# PT_2016_PB_4lyr_Rev2.net
KiCad netlist of a schematic drawn in EAGLE
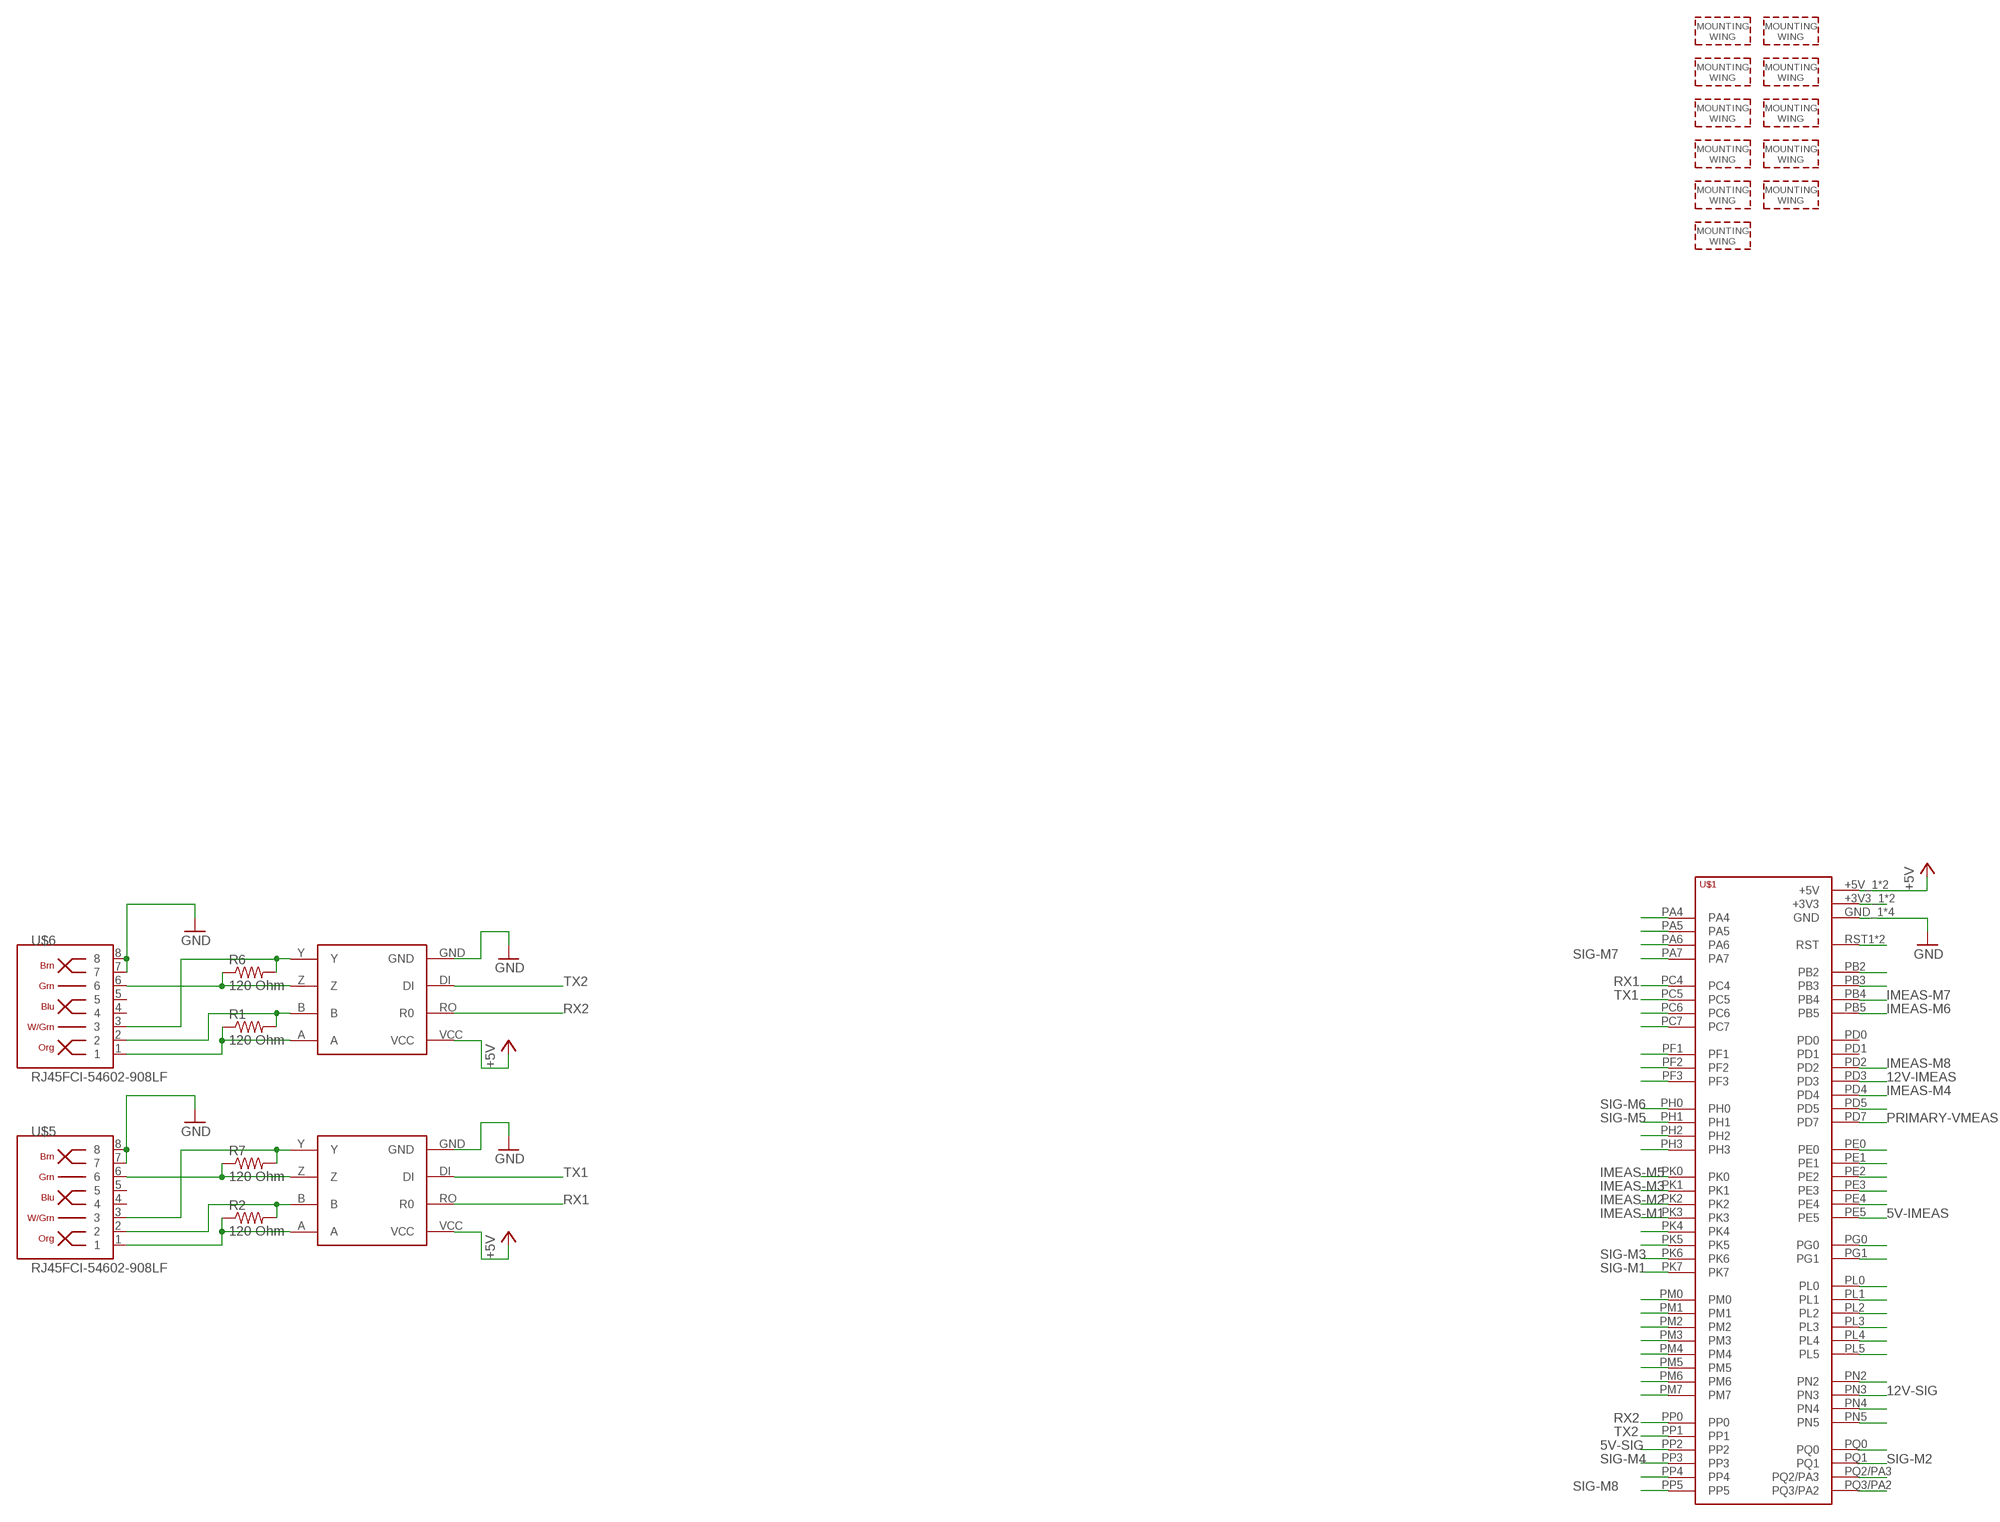
[diagram p0: schematic, sheet 1, part 1 of 3]
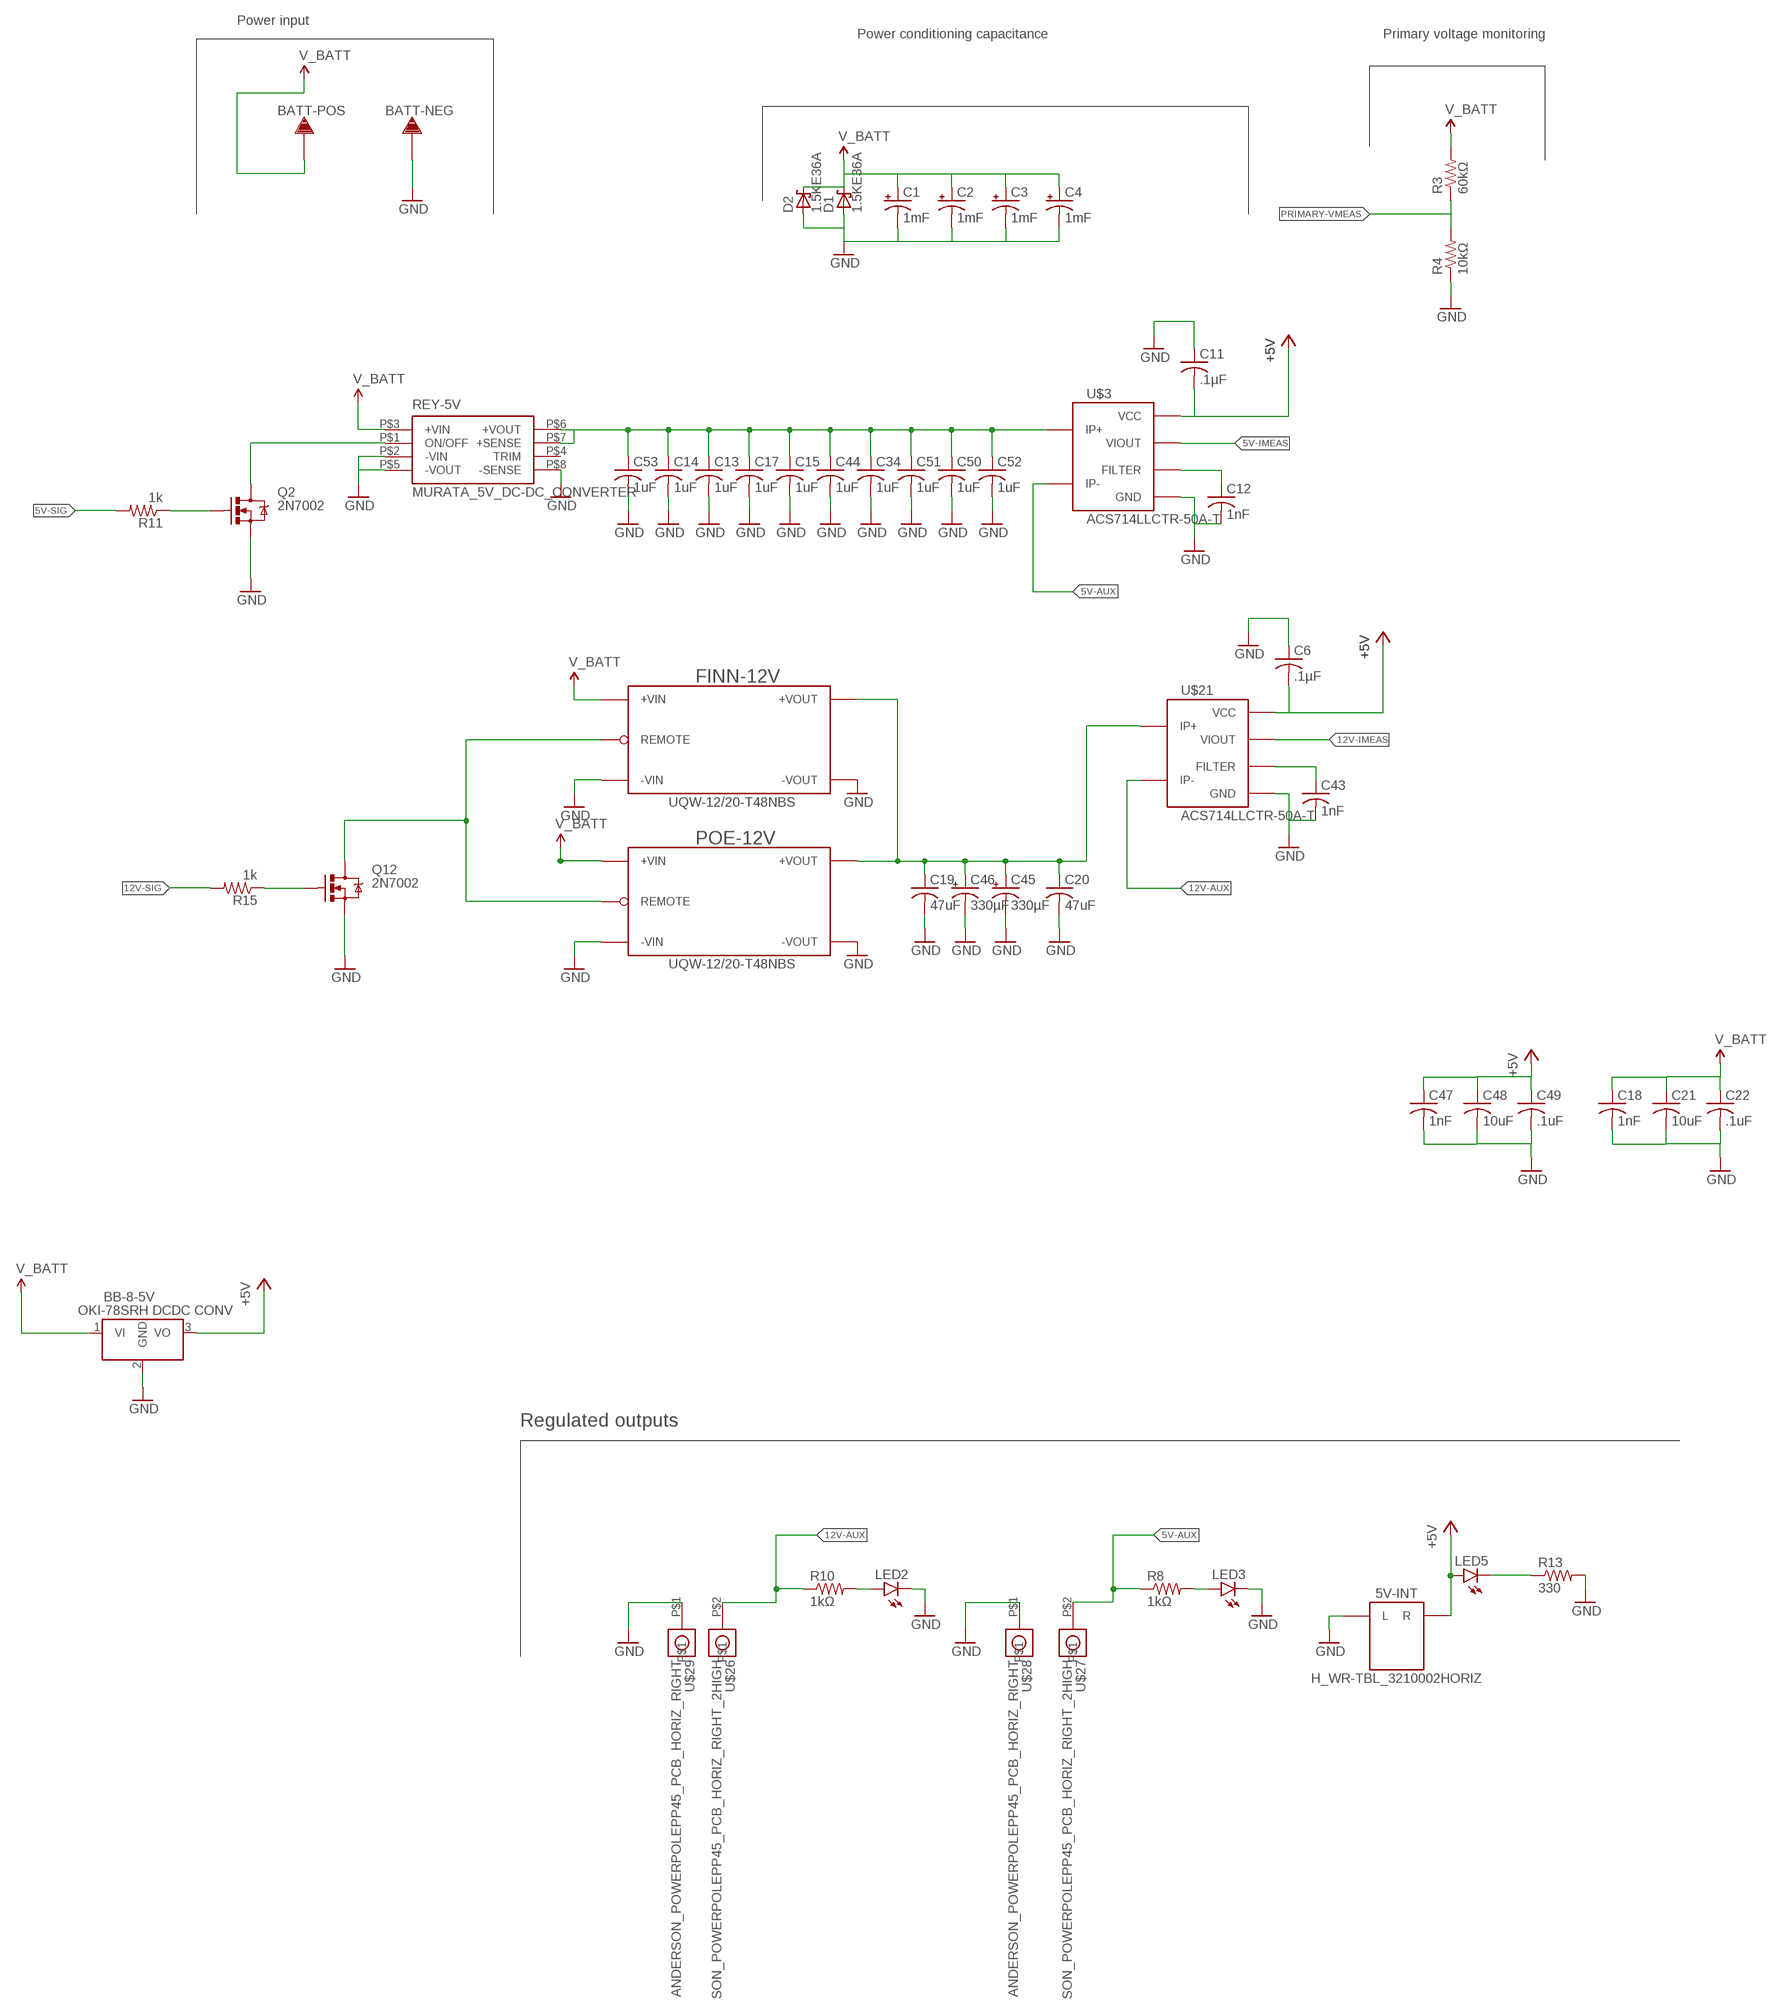
[diagram p1: schematic, sheet 1, part 2 of 3]
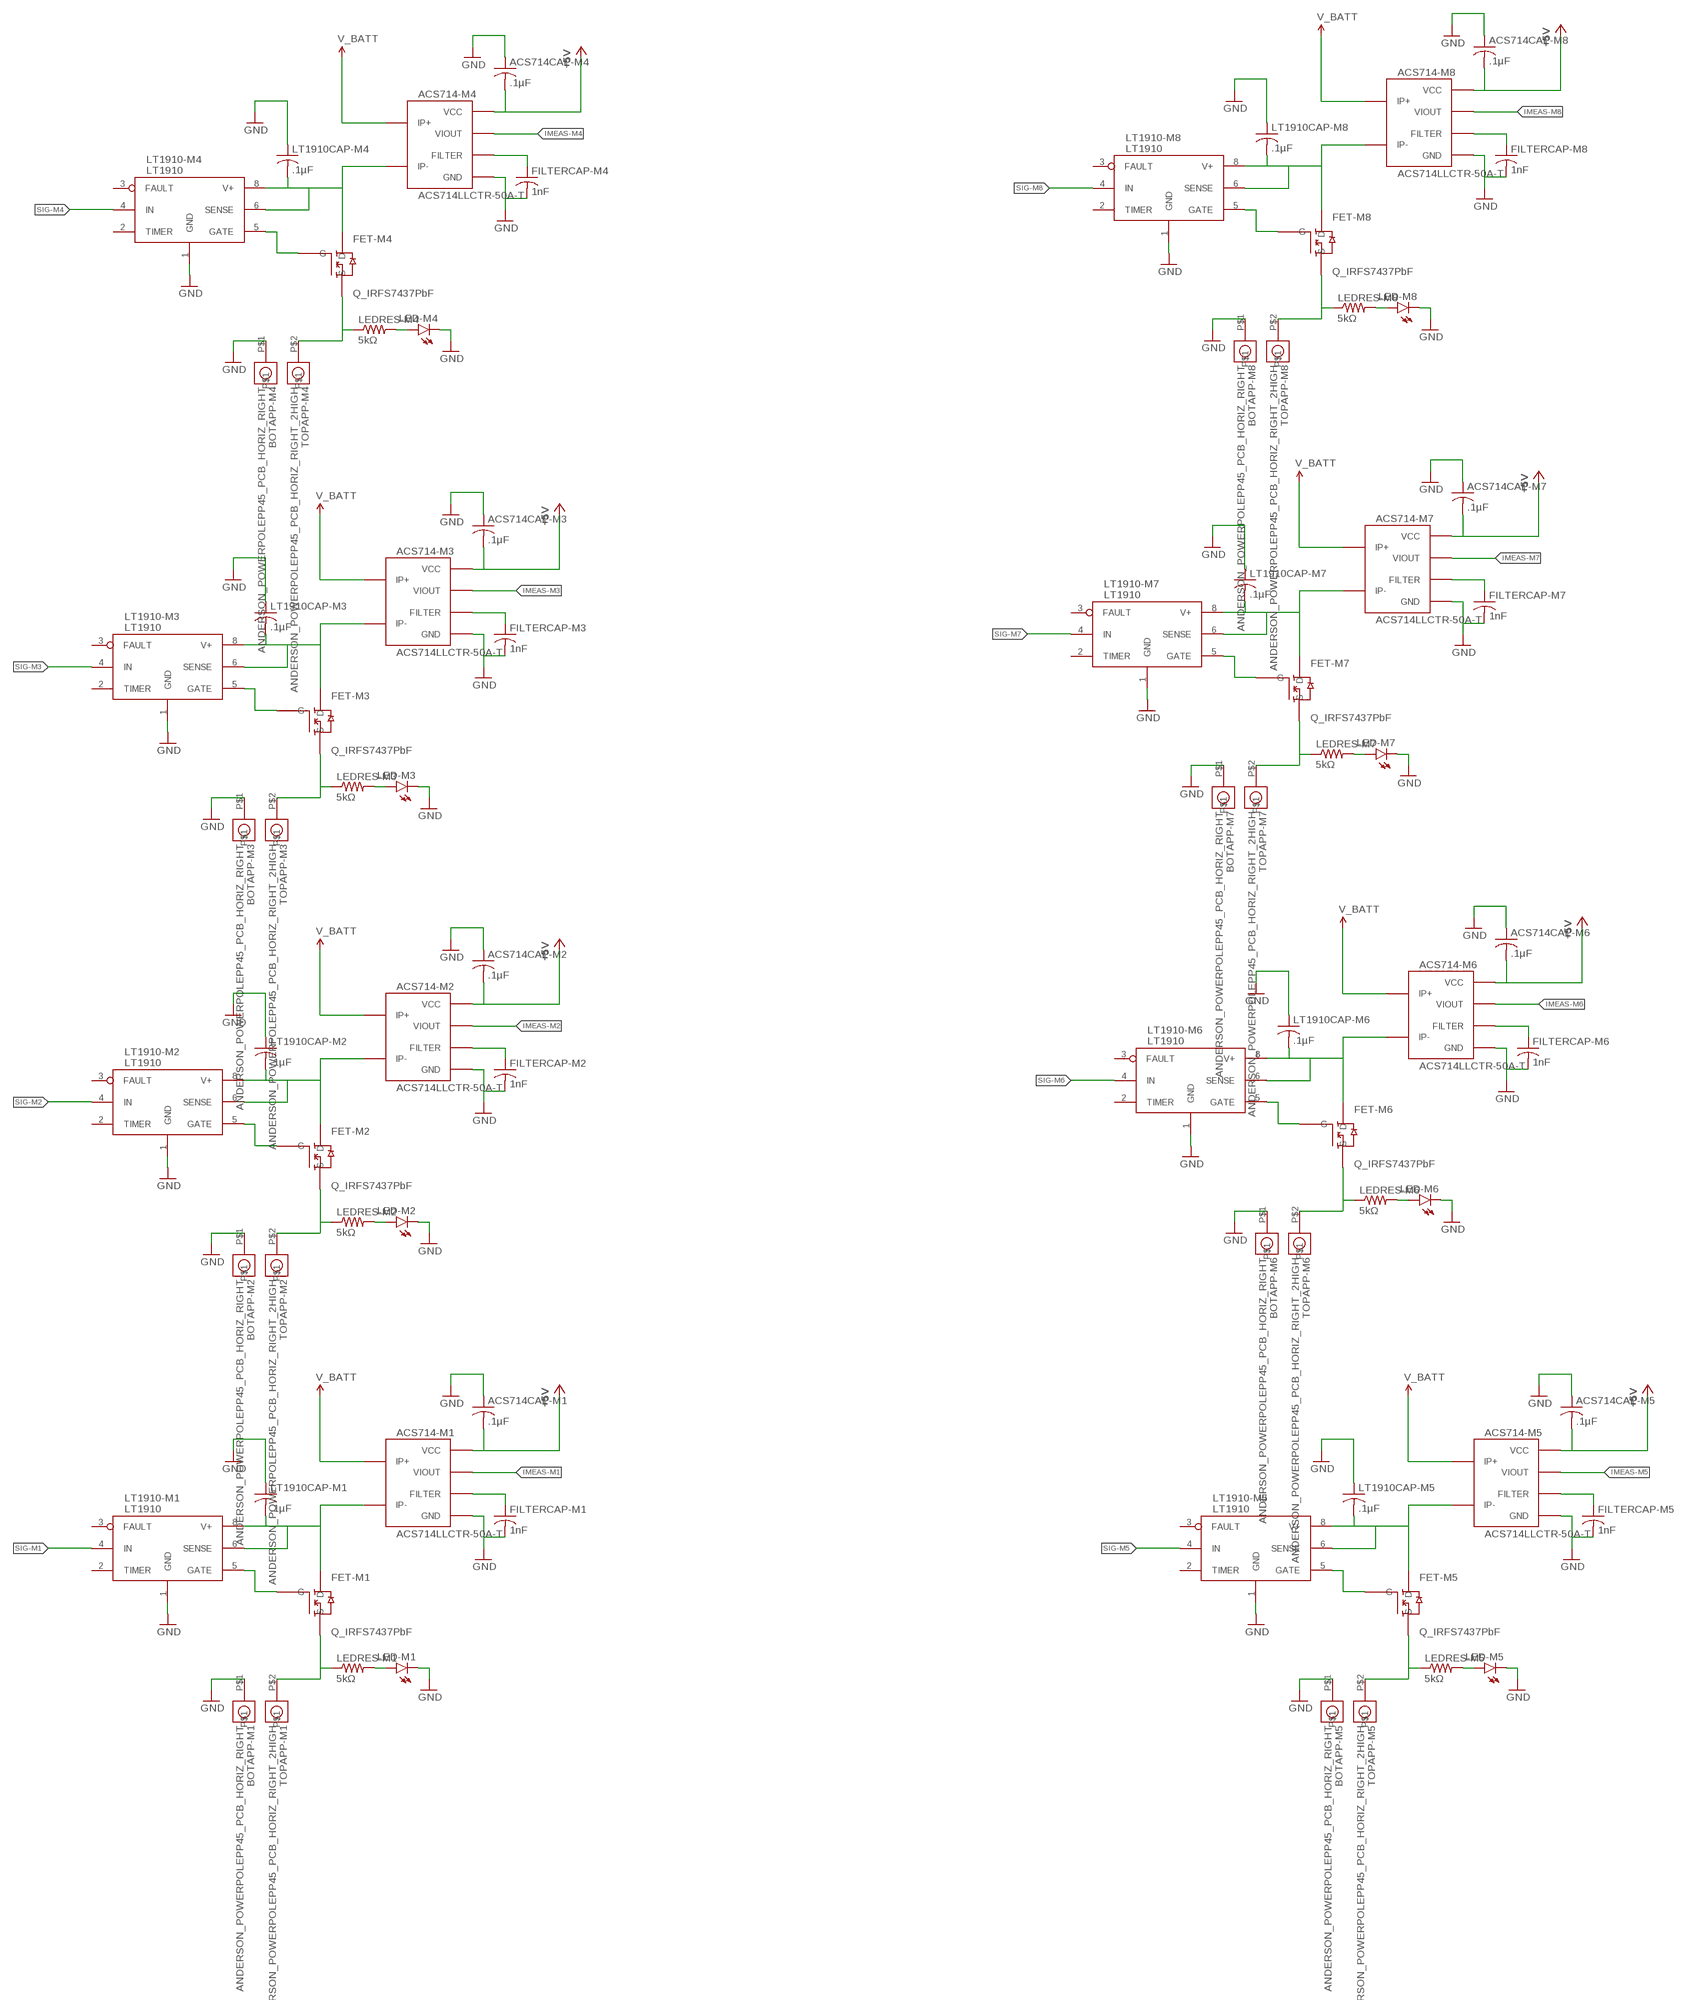
[diagram p2: schematic, sheet 1, part 3 of 3]

(export (version "E")
  (design (tool "Eeschema 10.0.6"))
  (components
    (comp (ref "5V-INT")
      (value "H_WR-TBL_3210002HORIZ")
      (footprint "eagle-import:691322110002")
      (libsource (lib "eagle-import") (part "H_WR-TBL_3210002HORIZ"))
    )
    (comp (ref "ACS714-M1")
      (value "ACS714LLCTR-50A-T")
      (footprint "eagle-import:SOIC8_ACS711")
      (libsource (lib "eagle-import") (part "Q_ACS714"))
    )
    (comp (ref "ACS714-M2")
      (value "ACS714LLCTR-50A-T")
      (footprint "eagle-import:SOIC8_ACS711")
      (libsource (lib "eagle-import") (part "Q_ACS714"))
    )
    (comp (ref "ACS714-M3")
      (value "ACS714LLCTR-50A-T")
      (footprint "eagle-import:SOIC8_ACS711")
      (libsource (lib "eagle-import") (part "Q_ACS714"))
    )
    (comp (ref "ACS714-M4")
      (value "ACS714LLCTR-50A-T")
      (footprint "eagle-import:SOIC8_ACS711")
      (libsource (lib "eagle-import") (part "Q_ACS714"))
    )
    (comp (ref "ACS714-M5")
      (value "ACS714LLCTR-50A-T")
      (footprint "eagle-import:SOIC8_ACS711")
      (libsource (lib "eagle-import") (part "Q_ACS714"))
    )
    (comp (ref "ACS714-M6")
      (value "ACS714LLCTR-50A-T")
      (footprint "eagle-import:SOIC8_ACS711")
      (libsource (lib "eagle-import") (part "Q_ACS714"))
    )
    (comp (ref "ACS714-M7")
      (value "ACS714LLCTR-50A-T")
      (footprint "eagle-import:SOIC8_ACS711")
      (libsource (lib "eagle-import") (part "Q_ACS714"))
    )
    (comp (ref "ACS714-M8")
      (value "ACS714LLCTR-50A-T")
      (footprint "eagle-import:SOIC8_ACS711")
      (libsource (lib "eagle-import") (part "Q_ACS714"))
    )
    (comp (ref "ACS714CAP-M1")
      (value ".1µF")
      (footprint "eagle-import:C1206")
      (libsource (lib "eagle-import") (part "C-USC1206"))
    )
    (comp (ref "ACS714CAP-M2")
      (value ".1µF")
      (footprint "eagle-import:C1206")
      (libsource (lib "eagle-import") (part "C-USC1206"))
    )
    (comp (ref "ACS714CAP-M3")
      (value ".1µF")
      (footprint "eagle-import:C1206")
      (libsource (lib "eagle-import") (part "C-USC1206"))
    )
    (comp (ref "ACS714CAP-M4")
      (value ".1µF")
      (footprint "eagle-import:C1206")
      (libsource (lib "eagle-import") (part "C-USC1206"))
    )
    (comp (ref "ACS714CAP-M5")
      (value ".1µF")
      (footprint "eagle-import:C1206")
      (libsource (lib "eagle-import") (part "C-USC1206"))
    )
    (comp (ref "ACS714CAP-M6")
      (value ".1µF")
      (footprint "eagle-import:C1206")
      (libsource (lib "eagle-import") (part "C-USC1206"))
    )
    (comp (ref "ACS714CAP-M7")
      (value ".1µF")
      (footprint "eagle-import:C1206")
      (libsource (lib "eagle-import") (part "C-USC1206"))
    )
    (comp (ref "ACS714CAP-M8")
      (value ".1µF")
      (footprint "eagle-import:C1206")
      (libsource (lib "eagle-import") (part "C-USC1206"))
    )
    (comp (ref "BATT-NEG")
      (value "TERMINAL_HOLE")
      (footprint "eagle-import:LARGE_TERMINAL_HOLE")
      (libsource (lib "eagle-import") (part "TERMINAL_HOLE"))
    )
    (comp (ref "BATT-POS")
      (value "TERMINAL_HOLE")
      (footprint "eagle-import:LARGE_TERMINAL_HOLE")
      (libsource (lib "eagle-import") (part "TERMINAL_HOLE"))
    )
    (comp (ref "BB-8-5V")
      (value "Q_OKI-78SR")
      (footprint "eagle-import:OKI-78SRH")
      (libsource (lib "eagle-import") (part "Q_OKI-78SR"))
    )
    (comp (ref "BOTAPP-M1")
      (value "ANDERSON_POWERPOLEPP45_PCB_HORIZ_RIGHT")
      (footprint "eagle-import:APP45_PCB_HORIZ_RIGHT")
      (libsource (lib "eagle-import") (part "ANDERSON_POWERPOLEPP45_PCB_HORIZ_RIGHT"))
    )
    (comp (ref "BOTAPP-M2")
      (value "ANDERSON_POWERPOLEPP45_PCB_HORIZ_RIGHT")
      (footprint "eagle-import:APP45_PCB_HORIZ_RIGHT")
      (libsource (lib "eagle-import") (part "ANDERSON_POWERPOLEPP45_PCB_HORIZ_RIGHT"))
    )
    (comp (ref "BOTAPP-M3")
      (value "ANDERSON_POWERPOLEPP45_PCB_HORIZ_RIGHT")
      (footprint "eagle-import:APP45_PCB_HORIZ_RIGHT")
      (libsource (lib "eagle-import") (part "ANDERSON_POWERPOLEPP45_PCB_HORIZ_RIGHT"))
    )
    (comp (ref "BOTAPP-M4")
      (value "ANDERSON_POWERPOLEPP45_PCB_HORIZ_RIGHT")
      (footprint "eagle-import:APP45_PCB_HORIZ_RIGHT")
      (libsource (lib "eagle-import") (part "ANDERSON_POWERPOLEPP45_PCB_HORIZ_RIGHT"))
    )
    (comp (ref "BOTAPP-M5")
      (value "ANDERSON_POWERPOLEPP45_PCB_HORIZ_RIGHT")
      (footprint "eagle-import:APP45_PCB_HORIZ_RIGHT")
      (libsource (lib "eagle-import") (part "ANDERSON_POWERPOLEPP45_PCB_HORIZ_RIGHT"))
    )
    (comp (ref "BOTAPP-M6")
      (value "ANDERSON_POWERPOLEPP45_PCB_HORIZ_RIGHT")
      (footprint "eagle-import:APP45_PCB_HORIZ_RIGHT")
      (libsource (lib "eagle-import") (part "ANDERSON_POWERPOLEPP45_PCB_HORIZ_RIGHT"))
    )
    (comp (ref "BOTAPP-M7")
      (value "ANDERSON_POWERPOLEPP45_PCB_HORIZ_RIGHT")
      (footprint "eagle-import:APP45_PCB_HORIZ_RIGHT")
      (libsource (lib "eagle-import") (part "ANDERSON_POWERPOLEPP45_PCB_HORIZ_RIGHT"))
    )
    (comp (ref "BOTAPP-M8")
      (value "ANDERSON_POWERPOLEPP45_PCB_HORIZ_RIGHT")
      (footprint "eagle-import:APP45_PCB_HORIZ_RIGHT")
      (libsource (lib "eagle-import") (part "ANDERSON_POWERPOLEPP45_PCB_HORIZ_RIGHT"))
    )
    (comp (ref "C1")
      (value "1mF")
      (footprint "eagle-import:C_12.5MM")
      (libsource (lib "eagle-import") (part "C_POL12.5MM_NORMAL"))
    )
    (comp (ref "C2")
      (value "1mF")
      (footprint "eagle-import:C_12.5MM")
      (libsource (lib "eagle-import") (part "C_POL12.5MM_NORMAL"))
    )
    (comp (ref "C3")
      (value "1mF")
      (footprint "eagle-import:C_12.5MM")
      (libsource (lib "eagle-import") (part "C_POL12.5MM_NORMAL"))
    )
    (comp (ref "C4")
      (value "1mF")
      (footprint "eagle-import:C_12.5MM")
      (libsource (lib "eagle-import") (part "C_POL12.5MM_NORMAL"))
    )
    (comp (ref "C6")
      (value ".1µF")
      (footprint "eagle-import:C1206")
      (libsource (lib "eagle-import") (part "C-USC1206"))
    )
    (comp (ref "C11")
      (value ".1µF")
      (footprint "eagle-import:C1206")
      (libsource (lib "eagle-import") (part "C-USC1206"))
    )
    (comp (ref "C12")
      (value "1nF")
      (footprint "eagle-import:C1206")
      (libsource (lib "eagle-import") (part "C-USC1206"))
    )
    (comp (ref "C13")
      (value "1uF")
      (footprint "eagle-import:C1206")
      (libsource (lib "eagle-import") (part "C-USC1206"))
    )
    (comp (ref "C14")
      (value "1uF")
      (footprint "eagle-import:C1206")
      (libsource (lib "eagle-import") (part "C-USC1206"))
    )
    (comp (ref "C15")
      (value "1uF")
      (footprint "eagle-import:C1206")
      (libsource (lib "eagle-import") (part "C-USC1206"))
    )
    (comp (ref "C17")
      (value "1uF")
      (footprint "eagle-import:C1206")
      (libsource (lib "eagle-import") (part "C-USC1206"))
    )
    (comp (ref "C18")
      (value "1nF")
      (footprint "eagle-import:C1206")
      (libsource (lib "eagle-import") (part "C-USC1206"))
    )
    (comp (ref "C19")
      (value "47uF")
      (footprint "eagle-import:C1206")
      (libsource (lib "eagle-import") (part "C-USC1206"))
    )
    (comp (ref "C20")
      (value "47uF")
      (footprint "eagle-import:C1206")
      (libsource (lib "eagle-import") (part "C-USC1206"))
    )
    (comp (ref "C21")
      (value "10uF")
      (footprint "eagle-import:C1206")
      (libsource (lib "eagle-import") (part "C-USC1206"))
    )
    (comp (ref "C22")
      (value ".1uF")
      (footprint "eagle-import:C1206")
      (libsource (lib "eagle-import") (part "C-USC1206"))
    )
    (comp (ref "C34")
      (value "1uF")
      (footprint "eagle-import:C1206")
      (libsource (lib "eagle-import") (part "C-USC1206"))
    )
    (comp (ref "C43")
      (value "1nF")
      (footprint "eagle-import:C1206")
      (libsource (lib "eagle-import") (part "C-USC1206"))
    )
    (comp (ref "C44")
      (value "1uF")
      (footprint "eagle-import:C1206")
      (libsource (lib "eagle-import") (part "C-USC1206"))
    )
    (comp (ref "C45")
      (value "330µF")
      (footprint "eagle-import:E5-8,5")
      (libsource (lib "eagle-import") (part "CPOL-USE5-8.5"))
    )
    (comp (ref "C46")
      (value "330µF")
      (footprint "eagle-import:E5-8,5")
      (libsource (lib "eagle-import") (part "CPOL-USE5-8.5"))
    )
    (comp (ref "C47")
      (value "1nF")
      (footprint "eagle-import:C1206")
      (libsource (lib "eagle-import") (part "C-USC1206"))
    )
    (comp (ref "C48")
      (value "10uF")
      (footprint "eagle-import:C1206")
      (libsource (lib "eagle-import") (part "C-USC1206"))
    )
    (comp (ref "C49")
      (value ".1uF")
      (footprint "eagle-import:C1206")
      (libsource (lib "eagle-import") (part "C-USC1206"))
    )
    (comp (ref "C50")
      (value "1uF")
      (footprint "eagle-import:C1206")
      (libsource (lib "eagle-import") (part "C-USC1206"))
    )
    (comp (ref "C51")
      (value "1uF")
      (footprint "eagle-import:C1206")
      (libsource (lib "eagle-import") (part "C-USC1206"))
    )
    (comp (ref "C52")
      (value "1uF")
      (footprint "eagle-import:C1206")
      (libsource (lib "eagle-import") (part "C-USC1206"))
    )
    (comp (ref "C53")
      (value "1uF")
      (footprint "eagle-import:C1206")
      (libsource (lib "eagle-import") (part "C-USC1206"))
    )
    (comp (ref "D1")
      (value "1.5KE36A")
      (footprint "eagle-import:CB429-17")
      (libsource (lib "eagle-import") (part "15KEXX"))
    )
    (comp (ref "D2")
      (value "1.5KE36A")
      (footprint "eagle-import:CB429-17")
      (libsource (lib "eagle-import") (part "15KEXX"))
    )
    (comp (ref "FET-M1")
      (value "Q_IRFS7437PbF")
      (footprint "eagle-import:D2PACK")
      (libsource (lib "eagle-import") (part "Q_IRF7437SMD"))
    )
    (comp (ref "FET-M2")
      (value "Q_IRFS7437PbF")
      (footprint "eagle-import:D2PACK")
      (libsource (lib "eagle-import") (part "Q_IRF7437SMD"))
    )
    (comp (ref "FET-M3")
      (value "Q_IRFS7437PbF")
      (footprint "eagle-import:D2PACK")
      (libsource (lib "eagle-import") (part "Q_IRF7437SMD"))
    )
    (comp (ref "FET-M4")
      (value "Q_IRFS7437PbF")
      (footprint "eagle-import:D2PACK")
      (libsource (lib "eagle-import") (part "Q_IRF7437SMD"))
    )
    (comp (ref "FET-M5")
      (value "Q_IRFS7437PbF")
      (footprint "eagle-import:D2PACK")
      (libsource (lib "eagle-import") (part "Q_IRF7437SMD"))
    )
    (comp (ref "FET-M6")
      (value "Q_IRFS7437PbF")
      (footprint "eagle-import:D2PACK")
      (libsource (lib "eagle-import") (part "Q_IRF7437SMD"))
    )
    (comp (ref "FET-M7")
      (value "Q_IRFS7437PbF")
      (footprint "eagle-import:D2PACK")
      (libsource (lib "eagle-import") (part "Q_IRF7437SMD"))
    )
    (comp (ref "FET-M8")
      (value "Q_IRFS7437PbF")
      (footprint "eagle-import:D2PACK")
      (libsource (lib "eagle-import") (part "Q_IRF7437SMD"))
    )
    (comp (ref "FILTERCAP-M1")
      (value "1nF")
      (footprint "eagle-import:C1206")
      (libsource (lib "eagle-import") (part "C-USC1206"))
    )
    (comp (ref "FILTERCAP-M2")
      (value "1nF")
      (footprint "eagle-import:C1206")
      (libsource (lib "eagle-import") (part "C-USC1206"))
    )
    (comp (ref "FILTERCAP-M3")
      (value "1nF")
      (footprint "eagle-import:C1206")
      (libsource (lib "eagle-import") (part "C-USC1206"))
    )
    (comp (ref "FILTERCAP-M4")
      (value "1nF")
      (footprint "eagle-import:C1206")
      (libsource (lib "eagle-import") (part "C-USC1206"))
    )
    (comp (ref "FILTERCAP-M5")
      (value "1nF")
      (footprint "eagle-import:C1206")
      (libsource (lib "eagle-import") (part "C-USC1206"))
    )
    (comp (ref "FILTERCAP-M6")
      (value "1nF")
      (footprint "eagle-import:C1206")
      (libsource (lib "eagle-import") (part "C-USC1206"))
    )
    (comp (ref "FILTERCAP-M7")
      (value "1nF")
      (footprint "eagle-import:C1206")
      (libsource (lib "eagle-import") (part "C-USC1206"))
    )
    (comp (ref "FILTERCAP-M8")
      (value "1nF")
      (footprint "eagle-import:C1206")
      (libsource (lib "eagle-import") (part "C-USC1206"))
    )
    (comp (ref "FINN-12V")
      (value "UQW-12/20-T48NBS")
      (footprint "eagle-import:U-T48-QB-NO_TRIM")
      (libsource (lib "eagle-import") (part "UQW-12/20-T48NBS"))
    )
    (comp (ref "LED-M1")
      (value "LED1206")
      (footprint "eagle-import:LED-1206")
      (libsource (lib "eagle-import") (part "LED1206"))
    )
    (comp (ref "LED-M2")
      (value "LED1206")
      (footprint "eagle-import:LED-1206")
      (libsource (lib "eagle-import") (part "LED1206"))
    )
    (comp (ref "LED-M3")
      (value "LED1206")
      (footprint "eagle-import:LED-1206")
      (libsource (lib "eagle-import") (part "LED1206"))
    )
    (comp (ref "LED-M4")
      (value "LED1206")
      (footprint "eagle-import:LED-1206")
      (libsource (lib "eagle-import") (part "LED1206"))
    )
    (comp (ref "LED-M5")
      (value "LED1206")
      (footprint "eagle-import:LED-1206")
      (libsource (lib "eagle-import") (part "LED1206"))
    )
    (comp (ref "LED-M6")
      (value "LED1206")
      (footprint "eagle-import:LED-1206")
      (libsource (lib "eagle-import") (part "LED1206"))
    )
    (comp (ref "LED-M7")
      (value "LED1206")
      (footprint "eagle-import:LED-1206")
      (libsource (lib "eagle-import") (part "LED1206"))
    )
    (comp (ref "LED-M8")
      (value "LED1206")
      (footprint "eagle-import:LED-1206")
      (libsource (lib "eagle-import") (part "LED1206"))
    )
    (comp (ref "LED2")
      (value "LED1206")
      (footprint "eagle-import:LED-1206")
      (libsource (lib "eagle-import") (part "LED1206"))
    )
    (comp (ref "LED3")
      (value "LED1206")
      (footprint "eagle-import:LED-1206")
      (libsource (lib "eagle-import") (part "LED1206"))
    )
    (comp (ref "LED5")
      (value "LED1206")
      (footprint "eagle-import:LED-1206")
      (libsource (lib "eagle-import") (part "LED1206"))
    )
    (comp (ref "LEDRES-M1")
      (value "5kΩ")
      (footprint "eagle-import:1206")
      (libsource (lib "eagle-import") (part "RESISTOR1206"))
    )
    (comp (ref "LEDRES-M2")
      (value "5kΩ")
      (footprint "eagle-import:1206")
      (libsource (lib "eagle-import") (part "RESISTOR1206"))
    )
    (comp (ref "LEDRES-M3")
      (value "5kΩ")
      (footprint "eagle-import:1206")
      (libsource (lib "eagle-import") (part "RESISTOR1206"))
    )
    (comp (ref "LEDRES-M4")
      (value "5kΩ")
      (footprint "eagle-import:1206")
      (libsource (lib "eagle-import") (part "RESISTOR1206"))
    )
    (comp (ref "LEDRES-M5")
      (value "5kΩ")
      (footprint "eagle-import:1206")
      (libsource (lib "eagle-import") (part "RESISTOR1206"))
    )
    (comp (ref "LEDRES-M6")
      (value "5kΩ")
      (footprint "eagle-import:1206")
      (libsource (lib "eagle-import") (part "RESISTOR1206"))
    )
    (comp (ref "LEDRES-M7")
      (value "5kΩ")
      (footprint "eagle-import:1206")
      (libsource (lib "eagle-import") (part "RESISTOR1206"))
    )
    (comp (ref "LEDRES-M8")
      (value "5kΩ")
      (footprint "eagle-import:1206")
      (libsource (lib "eagle-import") (part "RESISTOR1206"))
    )
    (comp (ref "LT1910-M1")
      (value "LT1910")
      (footprint "eagle-import:SO8")
      (libsource (lib "eagle-import") (part "LT1910"))
    )
    (comp (ref "LT1910-M2")
      (value "LT1910")
      (footprint "eagle-import:SO8")
      (libsource (lib "eagle-import") (part "LT1910"))
    )
    (comp (ref "LT1910-M3")
      (value "LT1910")
      (footprint "eagle-import:SO8")
      (libsource (lib "eagle-import") (part "LT1910"))
    )
    (comp (ref "LT1910-M4")
      (value "LT1910")
      (footprint "eagle-import:SO8")
      (libsource (lib "eagle-import") (part "LT1910"))
    )
    (comp (ref "LT1910-M5")
      (value "LT1910")
      (footprint "eagle-import:SO8")
      (libsource (lib "eagle-import") (part "LT1910"))
    )
    (comp (ref "LT1910-M6")
      (value "LT1910")
      (footprint "eagle-import:SO8")
      (libsource (lib "eagle-import") (part "LT1910"))
    )
    (comp (ref "LT1910-M7")
      (value "LT1910")
      (footprint "eagle-import:SO8")
      (libsource (lib "eagle-import") (part "LT1910"))
    )
    (comp (ref "LT1910-M8")
      (value "LT1910")
      (footprint "eagle-import:SO8")
      (libsource (lib "eagle-import") (part "LT1910"))
    )
    (comp (ref "LT1910CAP-M1")
      (value ".1µF")
      (footprint "eagle-import:C1206")
      (libsource (lib "eagle-import") (part "C-USC1206"))
    )
    (comp (ref "LT1910CAP-M2")
      (value ".1µF")
      (footprint "eagle-import:C1206")
      (libsource (lib "eagle-import") (part "C-USC1206"))
    )
    (comp (ref "LT1910CAP-M3")
      (value ".1µF")
      (footprint "eagle-import:C1206")
      (libsource (lib "eagle-import") (part "C-USC1206"))
    )
    (comp (ref "LT1910CAP-M4")
      (value ".1µF")
      (footprint "eagle-import:C1206")
      (libsource (lib "eagle-import") (part "C-USC1206"))
    )
    (comp (ref "LT1910CAP-M5")
      (value ".1µF")
      (footprint "eagle-import:C1206")
      (libsource (lib "eagle-import") (part "C-USC1206"))
    )
    (comp (ref "LT1910CAP-M6")
      (value ".1µF")
      (footprint "eagle-import:C1206")
      (libsource (lib "eagle-import") (part "C-USC1206"))
    )
    (comp (ref "LT1910CAP-M7")
      (value ".1µF")
      (footprint "eagle-import:C1206")
      (libsource (lib "eagle-import") (part "C-USC1206"))
    )
    (comp (ref "LT1910CAP-M8")
      (value ".1µF")
      (footprint "eagle-import:C1206")
      (libsource (lib "eagle-import") (part "C-USC1206"))
    )
    (comp (ref "POE-12V")
      (value "UQW-12/20-T48NBS")
      (footprint "eagle-import:U-T48-QB-NO_TRIM")
      (libsource (lib "eagle-import") (part "UQW-12/20-T48NBS"))
    )
    (comp (ref "Q2")
      (value "2N7002")
      (footprint "eagle-import:SOT323")
      (libsource (lib "eagle-import") (part "MOSFET-NCHANNEL2N7002PW"))
    )
    (comp (ref "Q12")
      (value "2N7002")
      (footprint "eagle-import:SOT323")
      (libsource (lib "eagle-import") (part "MOSFET-NCHANNEL2N7002PW"))
    )
    (comp (ref "R1")
      (value "120 Ohm")
      (footprint "eagle-import:1206")
      (libsource (lib "eagle-import") (part "RESISTOR1206"))
    )
    (comp (ref "R2")
      (value "120 Ohm")
      (footprint "eagle-import:1206")
      (libsource (lib "eagle-import") (part "RESISTOR1206"))
    )
    (comp (ref "R3")
      (value "60kΩ")
      (footprint "eagle-import:R1206")
      (libsource (lib "eagle-import") (part "R-US_R1206"))
    )
    (comp (ref "R4")
      (value "10kΩ")
      (footprint "eagle-import:R1206")
      (libsource (lib "eagle-import") (part "R-US_R1206"))
    )
    (comp (ref "R6")
      (value "120 Ohm")
      (footprint "eagle-import:1206")
      (libsource (lib "eagle-import") (part "RESISTOR1206"))
    )
    (comp (ref "R7")
      (value "120 Ohm")
      (footprint "eagle-import:1206")
      (libsource (lib "eagle-import") (part "RESISTOR1206"))
    )
    (comp (ref "R8")
      (value "1kΩ")
      (footprint "eagle-import:1206")
      (libsource (lib "eagle-import") (part "RESISTOR1206"))
    )
    (comp (ref "R10")
      (value "1kΩ")
      (footprint "eagle-import:1206")
      (libsource (lib "eagle-import") (part "RESISTOR1206"))
    )
    (comp (ref "R11")
      (value "1k")
      (footprint "eagle-import:R1206")
      (libsource (lib "eagle-import") (part "R-US_R1206"))
    )
    (comp (ref "R13")
      (value "330")
      (footprint "eagle-import:1206")
      (libsource (lib "eagle-import") (part "RESISTOR1206"))
    )
    (comp (ref "R15")
      (value "1k")
      (footprint "eagle-import:R1206")
      (libsource (lib "eagle-import") (part "R-US_R1206"))
    )
    (comp (ref "REY-5V")
      (value "MURATA_5V_DC-DC_CONVERTER")
      (footprint "eagle-import:MURATA_5V_DC-DC_CONVERTER")
      (libsource (lib "eagle-import") (part "MURATA_5V_DC-DC_CONVERTER"))
    )
    (comp (ref "TOPAPP-M1")
      (value "ANDERSON_POWERPOLEPP45_PCB_HORIZ_RIGHT_2HIGH")
      (footprint "eagle-import:APP45_PCB_HORIZ_RIGHT_2HIGH")
      (libsource (lib "eagle-import") (part "ANDERSON_POWERPOLEPP45_PCB_HORIZ_RIGHT_2HIGH"))
    )
    (comp (ref "TOPAPP-M2")
      (value "ANDERSON_POWERPOLEPP45_PCB_HORIZ_RIGHT_2HIGH")
      (footprint "eagle-import:APP45_PCB_HORIZ_RIGHT_2HIGH")
      (libsource (lib "eagle-import") (part "ANDERSON_POWERPOLEPP45_PCB_HORIZ_RIGHT_2HIGH"))
    )
    (comp (ref "TOPAPP-M3")
      (value "ANDERSON_POWERPOLEPP45_PCB_HORIZ_RIGHT_2HIGH")
      (footprint "eagle-import:APP45_PCB_HORIZ_RIGHT_2HIGH")
      (libsource (lib "eagle-import") (part "ANDERSON_POWERPOLEPP45_PCB_HORIZ_RIGHT_2HIGH"))
    )
    (comp (ref "TOPAPP-M4")
      (value "ANDERSON_POWERPOLEPP45_PCB_HORIZ_RIGHT_2HIGH")
      (footprint "eagle-import:APP45_PCB_HORIZ_RIGHT_2HIGH")
      (libsource (lib "eagle-import") (part "ANDERSON_POWERPOLEPP45_PCB_HORIZ_RIGHT_2HIGH"))
    )
    (comp (ref "TOPAPP-M5")
      (value "ANDERSON_POWERPOLEPP45_PCB_HORIZ_RIGHT_2HIGH")
      (footprint "eagle-import:APP45_PCB_HORIZ_RIGHT_2HIGH")
      (libsource (lib "eagle-import") (part "ANDERSON_POWERPOLEPP45_PCB_HORIZ_RIGHT_2HIGH"))
    )
    (comp (ref "TOPAPP-M6")
      (value "ANDERSON_POWERPOLEPP45_PCB_HORIZ_RIGHT_2HIGH")
      (footprint "eagle-import:APP45_PCB_HORIZ_RIGHT_2HIGH")
      (libsource (lib "eagle-import") (part "ANDERSON_POWERPOLEPP45_PCB_HORIZ_RIGHT_2HIGH"))
    )
    (comp (ref "TOPAPP-M7")
      (value "ANDERSON_POWERPOLEPP45_PCB_HORIZ_RIGHT_2HIGH")
      (footprint "eagle-import:APP45_PCB_HORIZ_RIGHT_2HIGH")
      (libsource (lib "eagle-import") (part "ANDERSON_POWERPOLEPP45_PCB_HORIZ_RIGHT_2HIGH"))
    )
    (comp (ref "TOPAPP-M8")
      (value "ANDERSON_POWERPOLEPP45_PCB_HORIZ_RIGHT_2HIGH")
      (footprint "eagle-import:APP45_PCB_HORIZ_RIGHT_2HIGH")
      (libsource (lib "eagle-import") (part "ANDERSON_POWERPOLEPP45_PCB_HORIZ_RIGHT_2HIGH"))
    )
    (comp (ref "U$1")
      (value "TIVA-C-CONNECTED")
      (footprint "eagle-import:TIVA-C-CONNECTED")
      (libsource (lib "eagle-import") (part "TIVA-C-CONNECTED"))
    )
    (comp (ref "U$2")
      (value "APP_MOUTING_WINGHORIZ")
      (footprint "eagle-import:APP45_MOUNTING_WING_HORIZ")
      (libsource (lib "eagle-import") (part "APP_MOUTING_WINGHORIZ"))
    )
    (comp (ref "U$3")
      (value "ACS714LLCTR-50A-T")
      (footprint "eagle-import:SOIC8_ACS711")
      (libsource (lib "eagle-import") (part "Q_ACS714"))
    )
    (comp (ref "U$4")
      (value "APP_MOUTING_WINGHORIZ")
      (footprint "eagle-import:APP45_MOUNTING_WING_HORIZ")
      (libsource (lib "eagle-import") (part "APP_MOUTING_WINGHORIZ"))
    )
    (comp (ref "U$5")
      (value "RJ45FCI-54602-908LF")
      (footprint "eagle-import:FCI-54602-908LF")
      (libsource (lib "eagle-import") (part "RJ45FCI-54602-908LF"))
    )
    (comp (ref "U$6")
      (value "RJ45FCI-54602-908LF")
      (footprint "eagle-import:FCI-54602-908LF")
      (libsource (lib "eagle-import") (part "RJ45FCI-54602-908LF"))
    )
    (comp (ref "U$12")
      (value "MAX3077")
      (footprint "eagle-import:MAX3070E")
      (libsource (lib "eagle-import") (part "MAX3077"))
    )
    (comp (ref "U$21")
      (value "ACS714LLCTR-50A-T")
      (footprint "eagle-import:SOIC8_ACS711")
      (libsource (lib "eagle-import") (part "Q_ACS714"))
    )
    (comp (ref "U$24")
      (value "MAX3077")
      (footprint "eagle-import:MAX3070E")
      (libsource (lib "eagle-import") (part "MAX3077"))
    )
    (comp (ref "U$25")
      (value "APP_MOUTING_WINGHORIZ")
      (footprint "eagle-import:APP45_MOUNTING_WING_HORIZ")
      (libsource (lib "eagle-import") (part "APP_MOUTING_WINGHORIZ"))
    )
    (comp (ref "U$26")
      (value "ANDERSON_POWERPOLEPP45_PCB_HORIZ_RIGHT_2HIGH")
      (footprint "eagle-import:APP45_PCB_HORIZ_RIGHT_2HIGH")
      (libsource (lib "eagle-import") (part "ANDERSON_POWERPOLEPP45_PCB_HORIZ_RIGHT_2HIGH"))
    )
    (comp (ref "U$27")
      (value "ANDERSON_POWERPOLEPP45_PCB_HORIZ_RIGHT_2HIGH")
      (footprint "eagle-import:APP45_PCB_HORIZ_RIGHT_2HIGH")
      (libsource (lib "eagle-import") (part "ANDERSON_POWERPOLEPP45_PCB_HORIZ_RIGHT_2HIGH"))
    )
    (comp (ref "U$28")
      (value "ANDERSON_POWERPOLEPP45_PCB_HORIZ_RIGHT")
      (footprint "eagle-import:APP45_PCB_HORIZ_RIGHT")
      (libsource (lib "eagle-import") (part "ANDERSON_POWERPOLEPP45_PCB_HORIZ_RIGHT"))
    )
    (comp (ref "U$29")
      (value "ANDERSON_POWERPOLEPP45_PCB_HORIZ_RIGHT")
      (footprint "eagle-import:APP45_PCB_HORIZ_RIGHT")
      (libsource (lib "eagle-import") (part "ANDERSON_POWERPOLEPP45_PCB_HORIZ_RIGHT"))
    )
    (comp (ref "U$30")
      (value "APP_MOUTING_WINGHORIZ")
      (footprint "eagle-import:APP45_MOUNTING_WING_HORIZ")
      (libsource (lib "eagle-import") (part "APP_MOUTING_WINGHORIZ"))
    )
    (comp (ref "U$31")
      (value "APP_MOUTING_WINGHORIZ")
      (footprint "eagle-import:APP45_MOUNTING_WING_HORIZ")
      (libsource (lib "eagle-import") (part "APP_MOUTING_WINGHORIZ"))
    )
    (comp (ref "U$32")
      (value "APP_MOUTING_WINGHORIZ")
      (footprint "eagle-import:APP45_MOUNTING_WING_HORIZ")
      (libsource (lib "eagle-import") (part "APP_MOUTING_WINGHORIZ"))
    )
    (comp (ref "U$33")
      (value "APP_MOUTING_WINGHORIZ")
      (footprint "eagle-import:APP45_MOUNTING_WING_HORIZ")
      (libsource (lib "eagle-import") (part "APP_MOUTING_WINGHORIZ"))
    )
    (comp (ref "U$34")
      (value "APP_MOUTING_WINGHORIZ")
      (footprint "eagle-import:APP45_MOUNTING_WING_HORIZ")
      (libsource (lib "eagle-import") (part "APP_MOUTING_WINGHORIZ"))
    )
    (comp (ref "U$35")
      (value "APP_MOUTING_WINGHORIZ")
      (footprint "eagle-import:APP45_MOUNTING_WING_HORIZ")
      (libsource (lib "eagle-import") (part "APP_MOUTING_WINGHORIZ"))
    )
    (comp (ref "U$41")
      (value "APP_MOUTING_WINGHORIZ")
      (footprint "eagle-import:APP45_MOUNTING_WING_HORIZ")
      (libsource (lib "eagle-import") (part "APP_MOUTING_WINGHORIZ"))
    )
    (comp (ref "U$42")
      (value "APP_MOUTING_WINGHORIZ")
      (footprint "eagle-import:APP45_MOUNTING_WING_HORIZ")
      (libsource (lib "eagle-import") (part "APP_MOUTING_WINGHORIZ"))
    )
  )
  (nets
    (net (code "1") (name "+5V") (class "Default")
      (node (ref "5V-INT") (pin "R") (pinfunction "R_R") (pintype "bidirectional"))
      (node (ref "ACS714-M1") (pin "8") (pinfunction "VCC_8") (pintype "bidirectional"))
      (node (ref "ACS714-M2") (pin "8") (pinfunction "VCC_8") (pintype "bidirectional"))
      (node (ref "ACS714-M3") (pin "8") (pinfunction "VCC_8") (pintype "bidirectional"))
      (node (ref "ACS714-M4") (pin "8") (pinfunction "VCC_8") (pintype "bidirectional"))
      (node (ref "ACS714-M5") (pin "8") (pinfunction "VCC_8") (pintype "bidirectional"))
      (node (ref "ACS714-M6") (pin "8") (pinfunction "VCC_8") (pintype "bidirectional"))
      (node (ref "ACS714-M7") (pin "8") (pinfunction "VCC_8") (pintype "bidirectional"))
      (node (ref "ACS714-M8") (pin "8") (pinfunction "VCC_8") (pintype "bidirectional"))
      (node (ref "ACS714CAP-M1") (pin "2") (pinfunction "2_2") (pintype "passive"))
      (node (ref "ACS714CAP-M2") (pin "2") (pinfunction "2_2") (pintype "passive"))
      (node (ref "ACS714CAP-M3") (pin "2") (pinfunction "2_2") (pintype "passive"))
      (node (ref "ACS714CAP-M4") (pin "2") (pinfunction "2_2") (pintype "passive"))
      (node (ref "ACS714CAP-M5") (pin "2") (pinfunction "2_2") (pintype "passive"))
      (node (ref "ACS714CAP-M6") (pin "2") (pinfunction "2_2") (pintype "passive"))
      (node (ref "ACS714CAP-M7") (pin "2") (pinfunction "2_2") (pintype "passive"))
      (node (ref "ACS714CAP-M8") (pin "2") (pinfunction "2_2") (pintype "passive"))
      (node (ref "BB-8-5V") (pin "3") (pinfunction "VO_3") (pintype "bidirectional"))
      (node (ref "C11") (pin "2") (pinfunction "2_2") (pintype "passive"))
      (node (ref "C47") (pin "1") (pinfunction "1_1") (pintype "passive"))
      (node (ref "C48") (pin "1") (pinfunction "1_1") (pintype "passive"))
      (node (ref "C49") (pin "1") (pinfunction "1_1") (pintype "passive"))
      (node (ref "C6") (pin "2") (pinfunction "2_2") (pintype "passive"))
      (node (ref "LED5") (pin "A") (pinfunction "A_A") (pintype "passive"))
      (node (ref "U$1") (pin "+5V_1") (pinfunction "+5V_+5V_1") (pintype "bidirectional"))
      (node (ref "U$1") (pin "+5V_2") (pinfunction "+5V_+5V_2") (pintype "bidirectional"))
      (node (ref "U$12") (pin "VCC") (pinfunction "VCC_VCC") (pintype "bidirectional"))
      (node (ref "U$21") (pin "8") (pinfunction "VCC_8") (pintype "bidirectional"))
      (node (ref "U$24") (pin "VCC") (pinfunction "VCC_VCC") (pintype "bidirectional"))
      (node (ref "U$3") (pin "8") (pinfunction "VCC_8") (pintype "bidirectional"))
    )
    (net (code "2") (name "/RX1") (class "Default")
      (node (ref "U$1") (pin "PC4") (pinfunction "PC4_PC4") (pintype "bidirectional"))
      (node (ref "U$24") (pin "RO") (pinfunction "R0_RO") (pintype "bidirectional"))
    )
    (net (code "3") (name "/RX2") (class "Default")
      (node (ref "U$1") (pin "PP0") (pinfunction "PP0_PP0") (pintype "bidirectional"))
      (node (ref "U$12") (pin "RO") (pinfunction "R0_RO") (pintype "bidirectional"))
    )
    (net (code "4") (name "/TX1") (class "Default")
      (node (ref "U$1") (pin "PC5") (pinfunction "PC5_PC5") (pintype "bidirectional"))
      (node (ref "U$24") (pin "DI") (pinfunction "DI_DI") (pintype "bidirectional"))
    )
    (net (code "5") (name "/TX2") (class "Default")
      (node (ref "U$1") (pin "PP1") (pinfunction "PP1_PP1") (pintype "bidirectional"))
      (node (ref "U$12") (pin "DI") (pinfunction "DI_DI") (pintype "bidirectional"))
    )
    (net (code "6") (name "5V-AUX") (class "Default")
      (node (ref "R8") (pin "1") (pinfunction "1_1") (pintype "passive"))
      (node (ref "U$27") (pin "P$2") (pinfunction "P$1_P$2") (pintype "bidirectional"))
      (node (ref "U$3") (pin "4") (pinfunction "IP-_4") (pintype "bidirectional"))
    )
    (net (code "7") (name "5V-IMEAS") (class "Default")
      (node (ref "U$1") (pin "PE5") (pinfunction "PE5_PE5") (pintype "bidirectional"))
      (node (ref "U$3") (pin "7") (pinfunction "VIOUT_7") (pintype "bidirectional"))
    )
    (net (code "8") (name "5V-SIG") (class "Default")
      (node (ref "R11") (pin "2") (pinfunction "2_2") (pintype "passive"))
      (node (ref "U$1") (pin "PP2") (pinfunction "PP2_PP2") (pintype "bidirectional"))
    )
    (net (code "9") (name "12V-AUX") (class "Default")
      (node (ref "R10") (pin "1") (pinfunction "1_1") (pintype "passive"))
      (node (ref "U$21") (pin "4") (pinfunction "IP-_4") (pintype "bidirectional"))
      (node (ref "U$26") (pin "P$2") (pinfunction "P$1_P$2") (pintype "bidirectional"))
    )
    (net (code "10") (name "12V-IMEAS") (class "Default")
      (node (ref "U$1") (pin "PD3") (pinfunction "PD3_PD3") (pintype "bidirectional"))
      (node (ref "U$21") (pin "7") (pinfunction "VIOUT_7") (pintype "bidirectional"))
    )
    (net (code "11") (name "12V-SIG") (class "Default")
      (node (ref "R15") (pin "2") (pinfunction "2_2") (pintype "passive"))
      (node (ref "U$1") (pin "PN3") (pinfunction "PN3_PN3") (pintype "bidirectional"))
    )
    (net (code "12") (name "GND") (class "Default")
      (node (ref "5V-INT") (pin "L") (pinfunction "L_L") (pintype "bidirectional"))
      (node (ref "ACS714-M1") (pin "5") (pinfunction "GND_5") (pintype "bidirectional"))
      (node (ref "ACS714-M2") (pin "5") (pinfunction "GND_5") (pintype "bidirectional"))
      (node (ref "ACS714-M3") (pin "5") (pinfunction "GND_5") (pintype "bidirectional"))
      (node (ref "ACS714-M4") (pin "5") (pinfunction "GND_5") (pintype "bidirectional"))
      (node (ref "ACS714-M5") (pin "5") (pinfunction "GND_5") (pintype "bidirectional"))
      (node (ref "ACS714-M6") (pin "5") (pinfunction "GND_5") (pintype "bidirectional"))
      (node (ref "ACS714-M7") (pin "5") (pinfunction "GND_5") (pintype "bidirectional"))
      (node (ref "ACS714-M8") (pin "5") (pinfunction "GND_5") (pintype "bidirectional"))
      (node (ref "ACS714CAP-M1") (pin "1") (pinfunction "1_1") (pintype "passive"))
      (node (ref "ACS714CAP-M2") (pin "1") (pinfunction "1_1") (pintype "passive"))
      (node (ref "ACS714CAP-M3") (pin "1") (pinfunction "1_1") (pintype "passive"))
      (node (ref "ACS714CAP-M4") (pin "1") (pinfunction "1_1") (pintype "passive"))
      (node (ref "ACS714CAP-M5") (pin "1") (pinfunction "1_1") (pintype "passive"))
      (node (ref "ACS714CAP-M6") (pin "1") (pinfunction "1_1") (pintype "passive"))
      (node (ref "ACS714CAP-M7") (pin "1") (pinfunction "1_1") (pintype "passive"))
      (node (ref "ACS714CAP-M8") (pin "1") (pinfunction "1_1") (pintype "passive"))
      (node (ref "BATT-NEG") (pin "P$1") (pinfunction "P$1_P$1") (pintype "bidirectional"))
      (node (ref "BB-8-5V") (pin "2") (pinfunction "GND_2") (pintype "bidirectional"))
      (node (ref "BOTAPP-M1") (pin "P$1") (pinfunction "P$1_P$1") (pintype "bidirectional"))
      (node (ref "BOTAPP-M2") (pin "P$1") (pinfunction "P$1_P$1") (pintype "bidirectional"))
      (node (ref "BOTAPP-M3") (pin "P$1") (pinfunction "P$1_P$1") (pintype "bidirectional"))
      (node (ref "BOTAPP-M4") (pin "P$1") (pinfunction "P$1_P$1") (pintype "bidirectional"))
      (node (ref "BOTAPP-M5") (pin "P$1") (pinfunction "P$1_P$1") (pintype "bidirectional"))
      (node (ref "BOTAPP-M6") (pin "P$1") (pinfunction "P$1_P$1") (pintype "bidirectional"))
      (node (ref "BOTAPP-M7") (pin "P$1") (pinfunction "P$1_P$1") (pintype "bidirectional"))
      (node (ref "BOTAPP-M8") (pin "P$1") (pinfunction "P$1_P$1") (pintype "bidirectional"))
      (node (ref "C1") (pin "-") (pinfunction "-_-") (pintype "passive"))
      (node (ref "C11") (pin "1") (pinfunction "1_1") (pintype "passive"))
      (node (ref "C12") (pin "2") (pinfunction "2_2") (pintype "passive"))
      (node (ref "C13") (pin "2") (pinfunction "2_2") (pintype "passive"))
      (node (ref "C14") (pin "2") (pinfunction "2_2") (pintype "passive"))
      (node (ref "C15") (pin "2") (pinfunction "2_2") (pintype "passive"))
      (node (ref "C17") (pin "2") (pinfunction "2_2") (pintype "passive"))
      (node (ref "C18") (pin "2") (pinfunction "2_2") (pintype "passive"))
      (node (ref "C19") (pin "2") (pinfunction "2_2") (pintype "passive"))
      (node (ref "C2") (pin "-") (pinfunction "-_-") (pintype "passive"))
      (node (ref "C20") (pin "2") (pinfunction "2_2") (pintype "passive"))
      (node (ref "C21") (pin "2") (pinfunction "2_2") (pintype "passive"))
      (node (ref "C22") (pin "2") (pinfunction "2_2") (pintype "passive"))
      (node (ref "C3") (pin "-") (pinfunction "-_-") (pintype "passive"))
      (node (ref "C34") (pin "2") (pinfunction "2_2") (pintype "passive"))
      (node (ref "C4") (pin "-") (pinfunction "-_-") (pintype "passive"))
      (node (ref "C43") (pin "2") (pinfunction "2_2") (pintype "passive"))
      (node (ref "C44") (pin "2") (pinfunction "2_2") (pintype "passive"))
      (node (ref "C45") (pin "-") (pinfunction "-_-") (pintype "passive"))
      (node (ref "C46") (pin "-") (pinfunction "-_-") (pintype "passive"))
      (node (ref "C47") (pin "2") (pinfunction "2_2") (pintype "passive"))
      (node (ref "C48") (pin "2") (pinfunction "2_2") (pintype "passive"))
      (node (ref "C49") (pin "2") (pinfunction "2_2") (pintype "passive"))
      (node (ref "C50") (pin "2") (pinfunction "2_2") (pintype "passive"))
      (node (ref "C51") (pin "2") (pinfunction "2_2") (pintype "passive"))
      (node (ref "C52") (pin "2") (pinfunction "2_2") (pintype "passive"))
      (node (ref "C53") (pin "2") (pinfunction "2_2") (pintype "passive"))
      (node (ref "C6") (pin "1") (pinfunction "1_1") (pintype "passive"))
      (node (ref "D1") (pin "A") (pinfunction "A_A") (pintype "passive"))
      (node (ref "D2") (pin "A") (pinfunction "A_A") (pintype "passive"))
      (node (ref "FILTERCAP-M1") (pin "2") (pinfunction "2_2") (pintype "passive"))
      (node (ref "FILTERCAP-M2") (pin "2") (pinfunction "2_2") (pintype "passive"))
      (node (ref "FILTERCAP-M3") (pin "2") (pinfunction "2_2") (pintype "passive"))
      (node (ref "FILTERCAP-M4") (pin "2") (pinfunction "2_2") (pintype "passive"))
      (node (ref "FILTERCAP-M5") (pin "2") (pinfunction "2_2") (pintype "passive"))
      (node (ref "FILTERCAP-M6") (pin "2") (pinfunction "2_2") (pintype "passive"))
      (node (ref "FILTERCAP-M7") (pin "2") (pinfunction "2_2") (pintype "passive"))
      (node (ref "FILTERCAP-M8") (pin "2") (pinfunction "2_2") (pintype "passive"))
      (node (ref "FINN-12V") (pin "3") (pinfunction "-VIN_3") (pintype "bidirectional"))
      (node (ref "FINN-12V") (pin "4") (pinfunction "-VOUT_4") (pintype "bidirectional"))
      (node (ref "LED-M1") (pin "C") (pinfunction "C_C") (pintype "passive"))
      (node (ref "LED-M2") (pin "C") (pinfunction "C_C") (pintype "passive"))
      (node (ref "LED-M3") (pin "C") (pinfunction "C_C") (pintype "passive"))
      (node (ref "LED-M4") (pin "C") (pinfunction "C_C") (pintype "passive"))
      (node (ref "LED-M5") (pin "C") (pinfunction "C_C") (pintype "passive"))
      (node (ref "LED-M6") (pin "C") (pinfunction "C_C") (pintype "passive"))
      (node (ref "LED-M7") (pin "C") (pinfunction "C_C") (pintype "passive"))
      (node (ref "LED-M8") (pin "C") (pinfunction "C_C") (pintype "passive"))
      (node (ref "LED2") (pin "C") (pinfunction "C_C") (pintype "passive"))
      (node (ref "LED3") (pin "C") (pinfunction "C_C") (pintype "passive"))
      (node (ref "LT1910-M1") (pin "1") (pinfunction "GND_1") (pintype "bidirectional"))
      (node (ref "LT1910-M2") (pin "1") (pinfunction "GND_1") (pintype "bidirectional"))
      (node (ref "LT1910-M3") (pin "1") (pinfunction "GND_1") (pintype "bidirectional"))
      (node (ref "LT1910-M4") (pin "1") (pinfunction "GND_1") (pintype "bidirectional"))
      (node (ref "LT1910-M5") (pin "1") (pinfunction "GND_1") (pintype "bidirectional"))
      (node (ref "LT1910-M6") (pin "1") (pinfunction "GND_1") (pintype "bidirectional"))
      (node (ref "LT1910-M7") (pin "1") (pinfunction "GND_1") (pintype "bidirectional"))
      (node (ref "LT1910-M8") (pin "1") (pinfunction "GND_1") (pintype "bidirectional"))
      (node (ref "LT1910CAP-M1") (pin "1") (pinfunction "1_1") (pintype "passive"))
      (node (ref "LT1910CAP-M2") (pin "1") (pinfunction "1_1") (pintype "passive"))
      (node (ref "LT1910CAP-M3") (pin "1") (pinfunction "1_1") (pintype "passive"))
      (node (ref "LT1910CAP-M4") (pin "1") (pinfunction "1_1") (pintype "passive"))
      (node (ref "LT1910CAP-M5") (pin "1") (pinfunction "1_1") (pintype "passive"))
      (node (ref "LT1910CAP-M6") (pin "1") (pinfunction "1_1") (pintype "passive"))
      (node (ref "LT1910CAP-M7") (pin "1") (pinfunction "1_1") (pintype "passive"))
      (node (ref "LT1910CAP-M8") (pin "1") (pinfunction "1_1") (pintype "passive"))
      (node (ref "POE-12V") (pin "3") (pinfunction "-VIN_3") (pintype "bidirectional"))
      (node (ref "POE-12V") (pin "4") (pinfunction "-VOUT_4") (pintype "bidirectional"))
      (node (ref "Q12") (pin "2") (pinfunction "S_2") (pintype "passive"))
      (node (ref "Q2") (pin "2") (pinfunction "S_2") (pintype "passive"))
      (node (ref "R13") (pin "2") (pinfunction "2_2") (pintype "passive"))
      (node (ref "R4") (pin "1") (pinfunction "1_1") (pintype "passive"))
      (node (ref "REY-5V") (pin "P$2") (pinfunction "-VIN_P$2") (pintype "bidirectional"))
      (node (ref "REY-5V") (pin "P$5") (pinfunction "-VOUT_P$5") (pintype "bidirectional"))
      (node (ref "REY-5V") (pin "P$8") (pinfunction "-SENSE_P$8") (pintype "bidirectional"))
      (node (ref "U$1") (pin "GND_1") (pinfunction "GND_GND_1") (pintype "bidirectional"))
      (node (ref "U$1") (pin "GND_2") (pinfunction "GND_GND_2") (pintype "bidirectional"))
      (node (ref "U$1") (pin "GND_3") (pinfunction "GND_GND_3") (pintype "bidirectional"))
      (node (ref "U$1") (pin "GND_4") (pinfunction "GND_GND_4") (pintype "bidirectional"))
      (node (ref "U$12") (pin "GND") (pinfunction "GND_GND") (pintype "bidirectional"))
      (node (ref "U$21") (pin "5") (pinfunction "GND_5") (pintype "bidirectional"))
      (node (ref "U$24") (pin "GND") (pinfunction "GND_GND") (pintype "bidirectional"))
      (node (ref "U$28") (pin "P$1") (pinfunction "P$1_P$1") (pintype "bidirectional"))
      (node (ref "U$29") (pin "P$1") (pinfunction "P$1_P$1") (pintype "bidirectional"))
      (node (ref "U$3") (pin "5") (pinfunction "GND_5") (pintype "bidirectional"))
      (node (ref "U$5") (pin "7") (pinfunction "7_7") (pintype "bidirectional"))
      (node (ref "U$5") (pin "8") (pinfunction "8_8") (pintype "bidirectional"))
      (node (ref "U$6") (pin "7") (pinfunction "7_7") (pintype "bidirectional"))
      (node (ref "U$6") (pin "8") (pinfunction "8_8") (pintype "bidirectional"))
    )
    (net (code "13") (name "IMEAS-M1") (class "Default")
      (node (ref "ACS714-M1") (pin "7") (pinfunction "VIOUT_7") (pintype "bidirectional"))
      (node (ref "U$1") (pin "PK3") (pinfunction "PK3_PK3") (pintype "bidirectional"))
    )
    (net (code "14") (name "IMEAS-M2") (class "Default")
      (node (ref "ACS714-M2") (pin "7") (pinfunction "VIOUT_7") (pintype "bidirectional"))
      (node (ref "U$1") (pin "PK2") (pinfunction "PK2_PK2") (pintype "bidirectional"))
    )
    (net (code "15") (name "IMEAS-M3") (class "Default")
      (node (ref "ACS714-M3") (pin "7") (pinfunction "VIOUT_7") (pintype "bidirectional"))
      (node (ref "U$1") (pin "PK1") (pinfunction "PK1_PK1") (pintype "bidirectional"))
    )
    (net (code "16") (name "IMEAS-M4") (class "Default")
      (node (ref "ACS714-M4") (pin "7") (pinfunction "VIOUT_7") (pintype "bidirectional"))
      (node (ref "U$1") (pin "PD4") (pinfunction "PD4_PD4") (pintype "bidirectional"))
    )
    (net (code "17") (name "IMEAS-M5") (class "Default")
      (node (ref "ACS714-M5") (pin "7") (pinfunction "VIOUT_7") (pintype "bidirectional"))
      (node (ref "U$1") (pin "PK0") (pinfunction "PK0_PK0") (pintype "bidirectional"))
    )
    (net (code "18") (name "IMEAS-M6") (class "Default")
      (node (ref "ACS714-M6") (pin "7") (pinfunction "VIOUT_7") (pintype "bidirectional"))
      (node (ref "U$1") (pin "PB5") (pinfunction "PB5_PB5") (pintype "bidirectional"))
    )
    (net (code "19") (name "IMEAS-M7") (class "Default")
      (node (ref "ACS714-M7") (pin "7") (pinfunction "VIOUT_7") (pintype "bidirectional"))
      (node (ref "U$1") (pin "PB4") (pinfunction "PB4_PB4") (pintype "bidirectional"))
    )
    (net (code "20") (name "IMEAS-M8") (class "Default")
      (node (ref "ACS714-M8") (pin "7") (pinfunction "VIOUT_7") (pintype "bidirectional"))
      (node (ref "U$1") (pin "PD2") (pinfunction "PD2_PD2") (pintype "bidirectional"))
    )
    (net (code "21") (name "Net-(ACS714-M1-FILTER)") (class "Default")
      (node (ref "ACS714-M1") (pin "6") (pinfunction "FILTER_6") (pintype "bidirectional"))
      (node (ref "FILTERCAP-M1") (pin "1") (pinfunction "1_1") (pintype "passive"))
    )
    (net (code "22") (name "Net-(ACS714-M1-IP-)") (class "Default")
      (node (ref "ACS714-M1") (pin "4") (pinfunction "IP-_4") (pintype "bidirectional"))
      (node (ref "FET-M1") (pin "TAB") (pinfunction "D_TAB") (pintype "bidirectional"))
      (node (ref "LT1910-M1") (pin "6") (pinfunction "SENSE_6") (pintype "bidirectional"))
      (node (ref "LT1910-M1") (pin "8") (pinfunction "V+_8") (pintype "bidirectional"))
      (node (ref "LT1910CAP-M1") (pin "2") (pinfunction "2_2") (pintype "passive"))
    )
    (net (code "23") (name "Net-(ACS714-M2-FILTER)") (class "Default")
      (node (ref "ACS714-M2") (pin "6") (pinfunction "FILTER_6") (pintype "bidirectional"))
      (node (ref "FILTERCAP-M2") (pin "1") (pinfunction "1_1") (pintype "passive"))
    )
    (net (code "24") (name "Net-(ACS714-M2-IP-)") (class "Default")
      (node (ref "ACS714-M2") (pin "4") (pinfunction "IP-_4") (pintype "bidirectional"))
      (node (ref "FET-M2") (pin "TAB") (pinfunction "D_TAB") (pintype "bidirectional"))
      (node (ref "LT1910-M2") (pin "6") (pinfunction "SENSE_6") (pintype "bidirectional"))
      (node (ref "LT1910-M2") (pin "8") (pinfunction "V+_8") (pintype "bidirectional"))
      (node (ref "LT1910CAP-M2") (pin "2") (pinfunction "2_2") (pintype "passive"))
    )
    (net (code "25") (name "Net-(ACS714-M3-FILTER)") (class "Default")
      (node (ref "ACS714-M3") (pin "6") (pinfunction "FILTER_6") (pintype "bidirectional"))
      (node (ref "FILTERCAP-M3") (pin "1") (pinfunction "1_1") (pintype "passive"))
    )
    (net (code "26") (name "Net-(ACS714-M3-IP-)") (class "Default")
      (node (ref "ACS714-M3") (pin "4") (pinfunction "IP-_4") (pintype "bidirectional"))
      (node (ref "FET-M3") (pin "TAB") (pinfunction "D_TAB") (pintype "bidirectional"))
      (node (ref "LT1910-M3") (pin "6") (pinfunction "SENSE_6") (pintype "bidirectional"))
      (node (ref "LT1910-M3") (pin "8") (pinfunction "V+_8") (pintype "bidirectional"))
      (node (ref "LT1910CAP-M3") (pin "2") (pinfunction "2_2") (pintype "passive"))
    )
    (net (code "27") (name "Net-(ACS714-M4-FILTER)") (class "Default")
      (node (ref "ACS714-M4") (pin "6") (pinfunction "FILTER_6") (pintype "bidirectional"))
      (node (ref "FILTERCAP-M4") (pin "1") (pinfunction "1_1") (pintype "passive"))
    )
    (net (code "28") (name "Net-(ACS714-M4-IP-)") (class "Default")
      (node (ref "ACS714-M4") (pin "4") (pinfunction "IP-_4") (pintype "bidirectional"))
      (node (ref "FET-M4") (pin "TAB") (pinfunction "D_TAB") (pintype "bidirectional"))
      (node (ref "LT1910-M4") (pin "6") (pinfunction "SENSE_6") (pintype "bidirectional"))
      (node (ref "LT1910-M4") (pin "8") (pinfunction "V+_8") (pintype "bidirectional"))
      (node (ref "LT1910CAP-M4") (pin "2") (pinfunction "2_2") (pintype "passive"))
    )
    (net (code "29") (name "Net-(ACS714-M5-FILTER)") (class "Default")
      (node (ref "ACS714-M5") (pin "6") (pinfunction "FILTER_6") (pintype "bidirectional"))
      (node (ref "FILTERCAP-M5") (pin "1") (pinfunction "1_1") (pintype "passive"))
    )
    (net (code "30") (name "Net-(ACS714-M5-IP-)") (class "Default")
      (node (ref "ACS714-M5") (pin "4") (pinfunction "IP-_4") (pintype "bidirectional"))
      (node (ref "FET-M5") (pin "TAB") (pinfunction "D_TAB") (pintype "bidirectional"))
      (node (ref "LT1910-M5") (pin "6") (pinfunction "SENSE_6") (pintype "bidirectional"))
      (node (ref "LT1910-M5") (pin "8") (pinfunction "V+_8") (pintype "bidirectional"))
      (node (ref "LT1910CAP-M5") (pin "2") (pinfunction "2_2") (pintype "passive"))
    )
    (net (code "31") (name "Net-(ACS714-M6-FILTER)") (class "Default")
      (node (ref "ACS714-M6") (pin "6") (pinfunction "FILTER_6") (pintype "bidirectional"))
      (node (ref "FILTERCAP-M6") (pin "1") (pinfunction "1_1") (pintype "passive"))
    )
    (net (code "32") (name "Net-(ACS714-M6-IP-)") (class "Default")
      (node (ref "ACS714-M6") (pin "4") (pinfunction "IP-_4") (pintype "bidirectional"))
      (node (ref "FET-M6") (pin "TAB") (pinfunction "D_TAB") (pintype "bidirectional"))
      (node (ref "LT1910-M6") (pin "6") (pinfunction "SENSE_6") (pintype "bidirectional"))
      (node (ref "LT1910-M6") (pin "8") (pinfunction "V+_8") (pintype "bidirectional"))
      (node (ref "LT1910CAP-M6") (pin "2") (pinfunction "2_2") (pintype "passive"))
    )
    (net (code "33") (name "Net-(ACS714-M7-FILTER)") (class "Default")
      (node (ref "ACS714-M7") (pin "6") (pinfunction "FILTER_6") (pintype "bidirectional"))
      (node (ref "FILTERCAP-M7") (pin "1") (pinfunction "1_1") (pintype "passive"))
    )
    (net (code "34") (name "Net-(ACS714-M7-IP-)") (class "Default")
      (node (ref "ACS714-M7") (pin "4") (pinfunction "IP-_4") (pintype "bidirectional"))
      (node (ref "FET-M7") (pin "TAB") (pinfunction "D_TAB") (pintype "bidirectional"))
      (node (ref "LT1910-M7") (pin "6") (pinfunction "SENSE_6") (pintype "bidirectional"))
      (node (ref "LT1910-M7") (pin "8") (pinfunction "V+_8") (pintype "bidirectional"))
      (node (ref "LT1910CAP-M7") (pin "2") (pinfunction "2_2") (pintype "passive"))
    )
    (net (code "35") (name "Net-(ACS714-M8-FILTER)") (class "Default")
      (node (ref "ACS714-M8") (pin "6") (pinfunction "FILTER_6") (pintype "bidirectional"))
      (node (ref "FILTERCAP-M8") (pin "1") (pinfunction "1_1") (pintype "passive"))
    )
    (net (code "36") (name "Net-(ACS714-M8-IP-)") (class "Default")
      (node (ref "ACS714-M8") (pin "4") (pinfunction "IP-_4") (pintype "bidirectional"))
      (node (ref "FET-M8") (pin "TAB") (pinfunction "D_TAB") (pintype "bidirectional"))
      (node (ref "LT1910-M8") (pin "6") (pinfunction "SENSE_6") (pintype "bidirectional"))
      (node (ref "LT1910-M8") (pin "8") (pinfunction "V+_8") (pintype "bidirectional"))
      (node (ref "LT1910CAP-M8") (pin "2") (pinfunction "2_2") (pintype "passive"))
    )
    (net (code "37") (name "Net-(FET-M1-G)") (class "Default")
      (node (ref "FET-M1") (pin "1") (pinfunction "G_1") (pintype "bidirectional"))
      (node (ref "LT1910-M1") (pin "5") (pinfunction "GATE_5") (pintype "bidirectional"))
    )
    (net (code "38") (name "Net-(FET-M1-S)") (class "Default")
      (node (ref "FET-M1") (pin "2") (pinfunction "S_2") (pintype "bidirectional"))
      (node (ref "LEDRES-M1") (pin "1") (pinfunction "1_1") (pintype "passive"))
      (node (ref "TOPAPP-M1") (pin "P$2") (pinfunction "P$1_P$2") (pintype "bidirectional"))
    )
    (net (code "39") (name "Net-(FET-M2-G)") (class "Default")
      (node (ref "FET-M2") (pin "1") (pinfunction "G_1") (pintype "bidirectional"))
      (node (ref "LT1910-M2") (pin "5") (pinfunction "GATE_5") (pintype "bidirectional"))
    )
    (net (code "40") (name "Net-(FET-M2-S)") (class "Default")
      (node (ref "FET-M2") (pin "2") (pinfunction "S_2") (pintype "bidirectional"))
      (node (ref "LEDRES-M2") (pin "1") (pinfunction "1_1") (pintype "passive"))
      (node (ref "TOPAPP-M2") (pin "P$2") (pinfunction "P$1_P$2") (pintype "bidirectional"))
    )
    (net (code "41") (name "Net-(FET-M3-G)") (class "Default")
      (node (ref "FET-M3") (pin "1") (pinfunction "G_1") (pintype "bidirectional"))
      (node (ref "LT1910-M3") (pin "5") (pinfunction "GATE_5") (pintype "bidirectional"))
    )
    (net (code "42") (name "Net-(FET-M3-S)") (class "Default")
      (node (ref "FET-M3") (pin "2") (pinfunction "S_2") (pintype "bidirectional"))
      (node (ref "LEDRES-M3") (pin "1") (pinfunction "1_1") (pintype "passive"))
      (node (ref "TOPAPP-M3") (pin "P$2") (pinfunction "P$1_P$2") (pintype "bidirectional"))
    )
    (net (code "43") (name "Net-(FET-M4-G)") (class "Default")
      (node (ref "FET-M4") (pin "1") (pinfunction "G_1") (pintype "bidirectional"))
      (node (ref "LT1910-M4") (pin "5") (pinfunction "GATE_5") (pintype "bidirectional"))
    )
    (net (code "44") (name "Net-(FET-M4-S)") (class "Default")
      (node (ref "FET-M4") (pin "2") (pinfunction "S_2") (pintype "bidirectional"))
      (node (ref "LEDRES-M4") (pin "1") (pinfunction "1_1") (pintype "passive"))
      (node (ref "TOPAPP-M4") (pin "P$2") (pinfunction "P$1_P$2") (pintype "bidirectional"))
    )
    (net (code "45") (name "Net-(FET-M5-G)") (class "Default")
      (node (ref "FET-M5") (pin "1") (pinfunction "G_1") (pintype "bidirectional"))
      (node (ref "LT1910-M5") (pin "5") (pinfunction "GATE_5") (pintype "bidirectional"))
    )
    (net (code "46") (name "Net-(FET-M5-S)") (class "Default")
      (node (ref "FET-M5") (pin "2") (pinfunction "S_2") (pintype "bidirectional"))
      (node (ref "LEDRES-M5") (pin "1") (pinfunction "1_1") (pintype "passive"))
      (node (ref "TOPAPP-M5") (pin "P$2") (pinfunction "P$1_P$2") (pintype "bidirectional"))
    )
    (net (code "47") (name "Net-(FET-M6-G)") (class "Default")
      (node (ref "FET-M6") (pin "1") (pinfunction "G_1") (pintype "bidirectional"))
      (node (ref "LT1910-M6") (pin "5") (pinfunction "GATE_5") (pintype "bidirectional"))
    )
    (net (code "48") (name "Net-(FET-M6-S)") (class "Default")
      (node (ref "FET-M6") (pin "2") (pinfunction "S_2") (pintype "bidirectional"))
      (node (ref "LEDRES-M6") (pin "1") (pinfunction "1_1") (pintype "passive"))
      (node (ref "TOPAPP-M6") (pin "P$2") (pinfunction "P$1_P$2") (pintype "bidirectional"))
    )
    (net (code "49") (name "Net-(FET-M7-G)") (class "Default")
      (node (ref "FET-M7") (pin "1") (pinfunction "G_1") (pintype "bidirectional"))
      (node (ref "LT1910-M7") (pin "5") (pinfunction "GATE_5") (pintype "bidirectional"))
    )
    (net (code "50") (name "Net-(FET-M7-S)") (class "Default")
      (node (ref "FET-M7") (pin "2") (pinfunction "S_2") (pintype "bidirectional"))
      (node (ref "LEDRES-M7") (pin "1") (pinfunction "1_1") (pintype "passive"))
      (node (ref "TOPAPP-M7") (pin "P$2") (pinfunction "P$1_P$2") (pintype "bidirectional"))
    )
    (net (code "51") (name "Net-(FET-M8-G)") (class "Default")
      (node (ref "FET-M8") (pin "1") (pinfunction "G_1") (pintype "bidirectional"))
      (node (ref "LT1910-M8") (pin "5") (pinfunction "GATE_5") (pintype "bidirectional"))
    )
    (net (code "52") (name "Net-(FET-M8-S)") (class "Default")
      (node (ref "FET-M8") (pin "2") (pinfunction "S_2") (pintype "bidirectional"))
      (node (ref "LEDRES-M8") (pin "1") (pinfunction "1_1") (pintype "passive"))
      (node (ref "TOPAPP-M8") (pin "P$2") (pinfunction "P$1_P$2") (pintype "bidirectional"))
    )
    (net (code "53") (name "Net-(FINN-12V-+VOUT)") (class "Default")
      (node (ref "C19") (pin "1") (pinfunction "1_1") (pintype "passive"))
      (node (ref "C20") (pin "1") (pinfunction "1_1") (pintype "passive"))
      (node (ref "C45") (pin "+") (pinfunction "+_+") (pintype "passive"))
      (node (ref "C46") (pin "+") (pinfunction "+_+") (pintype "passive"))
      (node (ref "FINN-12V") (pin "8") (pinfunction "+VOUT_8") (pintype "bidirectional"))
      (node (ref "POE-12V") (pin "8") (pinfunction "+VOUT_8") (pintype "bidirectional"))
      (node (ref "U$21") (pin "1") (pinfunction "IP+_1") (pintype "bidirectional"))
    )
    (net (code "54") (name "Net-(FINN-12V-REMOTE)") (class "Default")
      (node (ref "FINN-12V") (pin "2") (pinfunction "REMOTE_2") (pintype "bidirectional"))
      (node (ref "POE-12V") (pin "2") (pinfunction "REMOTE_2") (pintype "bidirectional"))
      (node (ref "Q12") (pin "3") (pinfunction "D_3") (pintype "passive"))
    )
    (net (code "55") (name "Net-(LED-M1-PadA)") (class "Default")
      (node (ref "LED-M1") (pin "A") (pinfunction "A_A") (pintype "passive"))
      (node (ref "LEDRES-M1") (pin "2") (pinfunction "2_2") (pintype "passive"))
    )
    (net (code "56") (name "Net-(LED-M2-PadA)") (class "Default")
      (node (ref "LED-M2") (pin "A") (pinfunction "A_A") (pintype "passive"))
      (node (ref "LEDRES-M2") (pin "2") (pinfunction "2_2") (pintype "passive"))
    )
    (net (code "57") (name "Net-(LED-M3-PadA)") (class "Default")
      (node (ref "LED-M3") (pin "A") (pinfunction "A_A") (pintype "passive"))
      (node (ref "LEDRES-M3") (pin "2") (pinfunction "2_2") (pintype "passive"))
    )
    (net (code "58") (name "Net-(LED-M4-PadA)") (class "Default")
      (node (ref "LED-M4") (pin "A") (pinfunction "A_A") (pintype "passive"))
      (node (ref "LEDRES-M4") (pin "2") (pinfunction "2_2") (pintype "passive"))
    )
    (net (code "59") (name "Net-(LED-M5-PadA)") (class "Default")
      (node (ref "LED-M5") (pin "A") (pinfunction "A_A") (pintype "passive"))
      (node (ref "LEDRES-M5") (pin "2") (pinfunction "2_2") (pintype "passive"))
    )
    (net (code "60") (name "Net-(LED-M6-PadA)") (class "Default")
      (node (ref "LED-M6") (pin "A") (pinfunction "A_A") (pintype "passive"))
      (node (ref "LEDRES-M6") (pin "2") (pinfunction "2_2") (pintype "passive"))
    )
    (net (code "61") (name "Net-(LED-M7-PadA)") (class "Default")
      (node (ref "LED-M7") (pin "A") (pinfunction "A_A") (pintype "passive"))
      (node (ref "LEDRES-M7") (pin "2") (pinfunction "2_2") (pintype "passive"))
    )
    (net (code "62") (name "Net-(LED-M8-PadA)") (class "Default")
      (node (ref "LED-M8") (pin "A") (pinfunction "A_A") (pintype "passive"))
      (node (ref "LEDRES-M8") (pin "2") (pinfunction "2_2") (pintype "passive"))
    )
    (net (code "63") (name "Net-(LED2-PadA)") (class "Default")
      (node (ref "LED2") (pin "A") (pinfunction "A_A") (pintype "passive"))
      (node (ref "R10") (pin "2") (pinfunction "2_2") (pintype "passive"))
    )
    (net (code "64") (name "Net-(LED3-PadA)") (class "Default")
      (node (ref "LED3") (pin "A") (pinfunction "A_A") (pintype "passive"))
      (node (ref "R8") (pin "2") (pinfunction "2_2") (pintype "passive"))
    )
    (net (code "65") (name "Net-(LED5-PadC)") (class "Default")
      (node (ref "LED5") (pin "C") (pinfunction "C_C") (pintype "passive"))
      (node (ref "R13") (pin "1") (pinfunction "1_1") (pintype "passive"))
    )
    (net (code "66") (name "Net-(Q2-D)") (class "Default")
      (node (ref "Q2") (pin "3") (pinfunction "D_3") (pintype "passive"))
      (node (ref "REY-5V") (pin "P$1") (pinfunction "ON/OFF_P$1") (pintype "bidirectional"))
    )
    (net (code "67") (name "Net-(Q2-G)") (class "Default")
      (node (ref "Q2") (pin "1") (pinfunction "G_1") (pintype "passive"))
      (node (ref "R11") (pin "1") (pinfunction "1_1") (pintype "passive"))
    )
    (net (code "68") (name "Net-(Q12-G)") (class "Default")
      (node (ref "Q12") (pin "1") (pinfunction "G_1") (pintype "passive"))
      (node (ref "R15") (pin "1") (pinfunction "1_1") (pintype "passive"))
    )
    (net (code "69") (name "Net-(R1-Pad1)") (class "Default")
      (node (ref "R1") (pin "1") (pinfunction "1_1") (pintype "passive"))
      (node (ref "U$12") (pin "A") (pinfunction "A_A") (pintype "bidirectional"))
      (node (ref "U$6") (pin "1") (pinfunction "1_1") (pintype "bidirectional"))
    )
    (net (code "70") (name "Net-(R1-Pad2)") (class "Default")
      (node (ref "R1") (pin "2") (pinfunction "2_2") (pintype "passive"))
      (node (ref "U$12") (pin "B") (pinfunction "B_B") (pintype "bidirectional"))
      (node (ref "U$6") (pin "2") (pinfunction "2_2") (pintype "bidirectional"))
    )
    (net (code "71") (name "Net-(R2-Pad1)") (class "Default")
      (node (ref "R2") (pin "1") (pinfunction "1_1") (pintype "passive"))
      (node (ref "U$24") (pin "A") (pinfunction "A_A") (pintype "bidirectional"))
      (node (ref "U$5") (pin "1") (pinfunction "1_1") (pintype "bidirectional"))
    )
    (net (code "72") (name "Net-(R2-Pad2)") (class "Default")
      (node (ref "R2") (pin "2") (pinfunction "2_2") (pintype "passive"))
      (node (ref "U$24") (pin "B") (pinfunction "B_B") (pintype "bidirectional"))
      (node (ref "U$5") (pin "2") (pinfunction "2_2") (pintype "bidirectional"))
    )
    (net (code "73") (name "Net-(R6-Pad1)") (class "Default")
      (node (ref "R6") (pin "1") (pinfunction "1_1") (pintype "passive"))
      (node (ref "U$12") (pin "Z") (pinfunction "Z_Z") (pintype "bidirectional"))
      (node (ref "U$6") (pin "6") (pinfunction "6_6") (pintype "bidirectional"))
    )
    (net (code "74") (name "Net-(R6-Pad2)") (class "Default")
      (node (ref "R6") (pin "2") (pinfunction "2_2") (pintype "passive"))
      (node (ref "U$12") (pin "Y") (pinfunction "Y_Y") (pintype "bidirectional"))
      (node (ref "U$6") (pin "3") (pinfunction "3_3") (pintype "bidirectional"))
    )
    (net (code "75") (name "Net-(R7-Pad1)") (class "Default")
      (node (ref "R7") (pin "1") (pinfunction "1_1") (pintype "passive"))
      (node (ref "U$24") (pin "Z") (pinfunction "Z_Z") (pintype "bidirectional"))
      (node (ref "U$5") (pin "6") (pinfunction "6_6") (pintype "bidirectional"))
    )
    (net (code "76") (name "Net-(R7-Pad2)") (class "Default")
      (node (ref "R7") (pin "2") (pinfunction "2_2") (pintype "passive"))
      (node (ref "U$24") (pin "Y") (pinfunction "Y_Y") (pintype "bidirectional"))
      (node (ref "U$5") (pin "3") (pinfunction "3_3") (pintype "bidirectional"))
    )
    (net (code "77") (name "Net-(REY-5V-+SENSE)") (class "Default")
      (node (ref "C13") (pin "1") (pinfunction "1_1") (pintype "passive"))
      (node (ref "C14") (pin "1") (pinfunction "1_1") (pintype "passive"))
      (node (ref "C15") (pin "1") (pinfunction "1_1") (pintype "passive"))
      (node (ref "C17") (pin "1") (pinfunction "1_1") (pintype "passive"))
      (node (ref "C34") (pin "1") (pinfunction "1_1") (pintype "passive"))
      (node (ref "C44") (pin "1") (pinfunction "1_1") (pintype "passive"))
      (node (ref "C50") (pin "1") (pinfunction "1_1") (pintype "passive"))
      (node (ref "C51") (pin "1") (pinfunction "1_1") (pintype "passive"))
      (node (ref "C52") (pin "1") (pinfunction "1_1") (pintype "passive"))
      (node (ref "C53") (pin "1") (pinfunction "1_1") (pintype "passive"))
      (node (ref "REY-5V") (pin "P$6") (pinfunction "+VOUT_P$6") (pintype "bidirectional"))
      (node (ref "REY-5V") (pin "P$7") (pinfunction "+SENSE_P$7") (pintype "bidirectional"))
      (node (ref "U$3") (pin "1") (pinfunction "IP+_1") (pintype "bidirectional"))
    )
    (net (code "78") (name "Net-(U$1-+3V3-Pad+3V3_1)") (class "Default")
      (node (ref "U$1") (pin "+3V3_1") (pinfunction "+3V3_+3V3_1") (pintype "bidirectional"))
      (node (ref "U$1") (pin "+3V3_2") (pinfunction "+3V3_+3V3_2") (pintype "bidirectional"))
    )
    (net (code "79") (name "Net-(U$1-RST-PadRST1)") (class "Default")
      (node (ref "U$1") (pin "RST1") (pinfunction "RST_RST1") (pintype "bidirectional"))
      (node (ref "U$1") (pin "RST_2") (pinfunction "RST_RST_2") (pintype "bidirectional"))
    )
    (net (code "80") (name "Net-(U$3-FILTER)") (class "Default")
      (node (ref "C12") (pin "1") (pinfunction "1_1") (pintype "passive"))
      (node (ref "U$3") (pin "6") (pinfunction "FILTER_6") (pintype "bidirectional"))
    )
    (net (code "81") (name "Net-(U$21-FILTER)") (class "Default")
      (node (ref "C43") (pin "1") (pinfunction "1_1") (pintype "passive"))
      (node (ref "U$21") (pin "6") (pinfunction "FILTER_6") (pintype "bidirectional"))
    )
    (net (code "82") (name "PRIMARY-VMEAS") (class "Default")
      (node (ref "R3") (pin "1") (pinfunction "1_1") (pintype "passive"))
      (node (ref "R4") (pin "2") (pinfunction "2_2") (pintype "passive"))
      (node (ref "U$1") (pin "PD7") (pinfunction "PD7_PD7") (pintype "bidirectional"))
    )
    (net (code "83") (name "SIG-M1") (class "Default")
      (node (ref "LT1910-M1") (pin "4") (pinfunction "IN_4") (pintype "bidirectional"))
      (node (ref "U$1") (pin "PK7") (pinfunction "PK7_PK7") (pintype "bidirectional"))
    )
    (net (code "84") (name "SIG-M2") (class "Default")
      (node (ref "LT1910-M2") (pin "4") (pinfunction "IN_4") (pintype "bidirectional"))
      (node (ref "U$1") (pin "PQ1") (pinfunction "PQ1_PQ1") (pintype "bidirectional"))
    )
    (net (code "85") (name "SIG-M3") (class "Default")
      (node (ref "LT1910-M3") (pin "4") (pinfunction "IN_4") (pintype "bidirectional"))
      (node (ref "U$1") (pin "PK6") (pinfunction "PK6_PK6") (pintype "bidirectional"))
    )
    (net (code "86") (name "SIG-M4") (class "Default")
      (node (ref "LT1910-M4") (pin "4") (pinfunction "IN_4") (pintype "bidirectional"))
      (node (ref "U$1") (pin "PP3") (pinfunction "PP3_PP3") (pintype "bidirectional"))
    )
    (net (code "87") (name "SIG-M5") (class "Default")
      (node (ref "LT1910-M5") (pin "4") (pinfunction "IN_4") (pintype "bidirectional"))
      (node (ref "U$1") (pin "PH1") (pinfunction "PH1_PH1") (pintype "bidirectional"))
    )
    (net (code "88") (name "SIG-M6") (class "Default")
      (node (ref "LT1910-M6") (pin "4") (pinfunction "IN_4") (pintype "bidirectional"))
      (node (ref "U$1") (pin "PH0") (pinfunction "PH0_PH0") (pintype "bidirectional"))
    )
    (net (code "89") (name "SIG-M7") (class "Default")
      (node (ref "LT1910-M7") (pin "4") (pinfunction "IN_4") (pintype "bidirectional"))
      (node (ref "U$1") (pin "PA7") (pinfunction "PA7_PA7") (pintype "bidirectional"))
    )
    (net (code "90") (name "SIG-M8") (class "Default")
      (node (ref "LT1910-M8") (pin "4") (pinfunction "IN_4") (pintype "bidirectional"))
      (node (ref "U$1") (pin "PP5") (pinfunction "PP5_PP5") (pintype "bidirectional"))
    )
    (net (code "91") (name "V_BATT") (class "Default")
      (node (ref "ACS714-M1") (pin "1") (pinfunction "IP+_1") (pintype "bidirectional"))
      (node (ref "ACS714-M2") (pin "1") (pinfunction "IP+_1") (pintype "bidirectional"))
      (node (ref "ACS714-M3") (pin "1") (pinfunction "IP+_1") (pintype "bidirectional"))
      (node (ref "ACS714-M4") (pin "1") (pinfunction "IP+_1") (pintype "bidirectional"))
      (node (ref "ACS714-M5") (pin "1") (pinfunction "IP+_1") (pintype "bidirectional"))
      (node (ref "ACS714-M6") (pin "1") (pinfunction "IP+_1") (pintype "bidirectional"))
      (node (ref "ACS714-M7") (pin "1") (pinfunction "IP+_1") (pintype "bidirectional"))
      (node (ref "ACS714-M8") (pin "1") (pinfunction "IP+_1") (pintype "bidirectional"))
      (node (ref "BATT-POS") (pin "P$1") (pinfunction "P$1_P$1") (pintype "bidirectional"))
      (node (ref "BB-8-5V") (pin "1") (pinfunction "VI_1") (pintype "bidirectional"))
      (node (ref "C1") (pin "+") (pinfunction "+_+") (pintype "passive"))
      (node (ref "C18") (pin "1") (pinfunction "1_1") (pintype "passive"))
      (node (ref "C2") (pin "+") (pinfunction "+_+") (pintype "passive"))
      (node (ref "C21") (pin "1") (pinfunction "1_1") (pintype "passive"))
      (node (ref "C22") (pin "1") (pinfunction "1_1") (pintype "passive"))
      (node (ref "C3") (pin "+") (pinfunction "+_+") (pintype "passive"))
      (node (ref "C4") (pin "+") (pinfunction "+_+") (pintype "passive"))
      (node (ref "D1") (pin "C") (pinfunction "C_C") (pintype "passive"))
      (node (ref "D2") (pin "C") (pinfunction "C_C") (pintype "passive"))
      (node (ref "FINN-12V") (pin "1") (pinfunction "+VIN_1") (pintype "bidirectional"))
      (node (ref "POE-12V") (pin "1") (pinfunction "+VIN_1") (pintype "bidirectional"))
      (node (ref "R3") (pin "2") (pinfunction "2_2") (pintype "passive"))
      (node (ref "REY-5V") (pin "P$3") (pinfunction "+VIN_P$3") (pintype "bidirectional"))
    )
    (net (code "92") (name "unconnected-(LT1910-M1-FAULT-Pad3)") (class "Default")
      (node (ref "LT1910-M1") (pin "3") (pinfunction "FAULT_3") (pintype "bidirectional"))
    )
    (net (code "93") (name "unconnected-(LT1910-M1-TIMER-Pad2)") (class "Default")
      (node (ref "LT1910-M1") (pin "2") (pinfunction "TIMER_2") (pintype "bidirectional"))
    )
    (net (code "94") (name "unconnected-(LT1910-M2-FAULT-Pad3)") (class "Default")
      (node (ref "LT1910-M2") (pin "3") (pinfunction "FAULT_3") (pintype "bidirectional"))
    )
    (net (code "95") (name "unconnected-(LT1910-M2-TIMER-Pad2)") (class "Default")
      (node (ref "LT1910-M2") (pin "2") (pinfunction "TIMER_2") (pintype "bidirectional"))
    )
    (net (code "96") (name "unconnected-(LT1910-M3-FAULT-Pad3)") (class "Default")
      (node (ref "LT1910-M3") (pin "3") (pinfunction "FAULT_3") (pintype "bidirectional"))
    )
    (net (code "97") (name "unconnected-(LT1910-M3-TIMER-Pad2)") (class "Default")
      (node (ref "LT1910-M3") (pin "2") (pinfunction "TIMER_2") (pintype "bidirectional"))
    )
    (net (code "98") (name "unconnected-(LT1910-M4-FAULT-Pad3)") (class "Default")
      (node (ref "LT1910-M4") (pin "3") (pinfunction "FAULT_3") (pintype "bidirectional"))
    )
    (net (code "99") (name "unconnected-(LT1910-M4-TIMER-Pad2)") (class "Default")
      (node (ref "LT1910-M4") (pin "2") (pinfunction "TIMER_2") (pintype "bidirectional"))
    )
    (net (code "100") (name "unconnected-(LT1910-M5-FAULT-Pad3)") (class "Default")
      (node (ref "LT1910-M5") (pin "3") (pinfunction "FAULT_3") (pintype "bidirectional"))
    )
    (net (code "101") (name "unconnected-(LT1910-M5-TIMER-Pad2)") (class "Default")
      (node (ref "LT1910-M5") (pin "2") (pinfunction "TIMER_2") (pintype "bidirectional"))
    )
    (net (code "102") (name "unconnected-(LT1910-M6-FAULT-Pad3)") (class "Default")
      (node (ref "LT1910-M6") (pin "3") (pinfunction "FAULT_3") (pintype "bidirectional"))
    )
    (net (code "103") (name "unconnected-(LT1910-M6-TIMER-Pad2)") (class "Default")
      (node (ref "LT1910-M6") (pin "2") (pinfunction "TIMER_2") (pintype "bidirectional"))
    )
    (net (code "104") (name "unconnected-(LT1910-M7-FAULT-Pad3)") (class "Default")
      (node (ref "LT1910-M7") (pin "3") (pinfunction "FAULT_3") (pintype "bidirectional"))
    )
    (net (code "105") (name "unconnected-(LT1910-M7-TIMER-Pad2)") (class "Default")
      (node (ref "LT1910-M7") (pin "2") (pinfunction "TIMER_2") (pintype "bidirectional"))
    )
    (net (code "106") (name "unconnected-(LT1910-M8-FAULT-Pad3)") (class "Default")
      (node (ref "LT1910-M8") (pin "3") (pinfunction "FAULT_3") (pintype "bidirectional"))
    )
    (net (code "107") (name "unconnected-(LT1910-M8-TIMER-Pad2)") (class "Default")
      (node (ref "LT1910-M8") (pin "2") (pinfunction "TIMER_2") (pintype "bidirectional"))
    )
    (net (code "108") (name "unconnected-(REY-5V-TRIM-PadP$4)") (class "Default")
      (node (ref "REY-5V") (pin "P$4") (pinfunction "TRIM_P$4") (pintype "bidirectional"))
    )
    (net (code "109") (name "unconnected-(U$1-PadPA4)") (class "Default")
      (node (ref "U$1") (pin "PA4") (pinfunction "PA4_PA4") (pintype "bidirectional"))
    )
    (net (code "110") (name "unconnected-(U$1-PadPA5)") (class "Default")
      (node (ref "U$1") (pin "PA5") (pinfunction "PA5_PA5") (pintype "bidirectional"))
    )
    (net (code "111") (name "unconnected-(U$1-PadPA6)") (class "Default")
      (node (ref "U$1") (pin "PA6") (pinfunction "PA6_PA6") (pintype "bidirectional"))
    )
    (net (code "112") (name "unconnected-(U$1-PadPB2)") (class "Default")
      (node (ref "U$1") (pin "PB2") (pinfunction "PB2_PB2") (pintype "bidirectional"))
    )
    (net (code "113") (name "unconnected-(U$1-PadPB3)") (class "Default")
      (node (ref "U$1") (pin "PB3") (pinfunction "PB3_PB3") (pintype "bidirectional"))
    )
    (net (code "114") (name "unconnected-(U$1-PadPC6)") (class "Default")
      (node (ref "U$1") (pin "PC6") (pinfunction "PC6_PC6") (pintype "bidirectional"))
    )
    (net (code "115") (name "unconnected-(U$1-PadPC7)") (class "Default")
      (node (ref "U$1") (pin "PC7") (pinfunction "PC7_PC7") (pintype "bidirectional"))
    )
    (net (code "116") (name "unconnected-(U$1-PadPD0)") (class "Default")
      (node (ref "U$1") (pin "PD0") (pinfunction "PD0_PD0") (pintype "bidirectional"))
    )
    (net (code "117") (name "unconnected-(U$1-PadPD1)") (class "Default")
      (node (ref "U$1") (pin "PD1") (pinfunction "PD1_PD1") (pintype "bidirectional"))
    )
    (net (code "118") (name "unconnected-(U$1-PadPD5)") (class "Default")
      (node (ref "U$1") (pin "PD5") (pinfunction "PD5_PD5") (pintype "bidirectional"))
    )
    (net (code "119") (name "unconnected-(U$1-PadPE0)") (class "Default")
      (node (ref "U$1") (pin "PE0") (pinfunction "PE0_PE0") (pintype "bidirectional"))
    )
    (net (code "120") (name "unconnected-(U$1-PadPE1)") (class "Default")
      (node (ref "U$1") (pin "PE1") (pinfunction "PE1_PE1") (pintype "bidirectional"))
    )
    (net (code "121") (name "unconnected-(U$1-PadPE2)") (class "Default")
      (node (ref "U$1") (pin "PE2") (pinfunction "PE2_PE2") (pintype "bidirectional"))
    )
    (net (code "122") (name "unconnected-(U$1-PadPE3)") (class "Default")
      (node (ref "U$1") (pin "PE3") (pinfunction "PE3_PE3") (pintype "bidirectional"))
    )
    (net (code "123") (name "unconnected-(U$1-PadPE4)") (class "Default")
      (node (ref "U$1") (pin "PE4") (pinfunction "PE4_PE4") (pintype "bidirectional"))
    )
    (net (code "124") (name "unconnected-(U$1-PadPF1)") (class "Default")
      (node (ref "U$1") (pin "PF1") (pinfunction "PF1_PF1") (pintype "bidirectional"))
    )
    (net (code "125") (name "unconnected-(U$1-PadPF2)") (class "Default")
      (node (ref "U$1") (pin "PF2") (pinfunction "PF2_PF2") (pintype "bidirectional"))
    )
    (net (code "126") (name "unconnected-(U$1-PadPF3)") (class "Default")
      (node (ref "U$1") (pin "PF3") (pinfunction "PF3_PF3") (pintype "bidirectional"))
    )
    (net (code "127") (name "unconnected-(U$1-PadPG0)") (class "Default")
      (node (ref "U$1") (pin "PG0") (pinfunction "PG0_PG0") (pintype "bidirectional"))
    )
    (net (code "128") (name "unconnected-(U$1-PadPG1)") (class "Default")
      (node (ref "U$1") (pin "PG1") (pinfunction "PG1_PG1") (pintype "bidirectional"))
    )
    (net (code "129") (name "unconnected-(U$1-PadPH2)") (class "Default")
      (node (ref "U$1") (pin "PH2") (pinfunction "PH2_PH2") (pintype "bidirectional"))
    )
    (net (code "130") (name "unconnected-(U$1-PadPH3)") (class "Default")
      (node (ref "U$1") (pin "PH3") (pinfunction "PH3_PH3") (pintype "bidirectional"))
    )
    (net (code "131") (name "unconnected-(U$1-PadPK4)") (class "Default")
      (node (ref "U$1") (pin "PK4") (pinfunction "PK4_PK4") (pintype "bidirectional"))
    )
    (net (code "132") (name "unconnected-(U$1-PadPK5)") (class "Default")
      (node (ref "U$1") (pin "PK5") (pinfunction "PK5_PK5") (pintype "bidirectional"))
    )
    (net (code "133") (name "unconnected-(U$1-PadPL0)") (class "Default")
      (node (ref "U$1") (pin "PL0") (pinfunction "PL0_PL0") (pintype "bidirectional"))
    )
    (net (code "134") (name "unconnected-(U$1-PadPL1)") (class "Default")
      (node (ref "U$1") (pin "PL1") (pinfunction "PL1_PL1") (pintype "bidirectional"))
    )
    (net (code "135") (name "unconnected-(U$1-PadPL2)") (class "Default")
      (node (ref "U$1") (pin "PL2") (pinfunction "PL2_PL2") (pintype "bidirectional"))
    )
    (net (code "136") (name "unconnected-(U$1-PadPL3)") (class "Default")
      (node (ref "U$1") (pin "PL3") (pinfunction "PL3_PL3") (pintype "bidirectional"))
    )
    (net (code "137") (name "unconnected-(U$1-PadPL4)") (class "Default")
      (node (ref "U$1") (pin "PL4") (pinfunction "PL4_PL4") (pintype "bidirectional"))
    )
    (net (code "138") (name "unconnected-(U$1-PadPL5)") (class "Default")
      (node (ref "U$1") (pin "PL5") (pinfunction "PL5_PL5") (pintype "bidirectional"))
    )
    (net (code "139") (name "unconnected-(U$1-PadPM0)") (class "Default")
      (node (ref "U$1") (pin "PM0") (pinfunction "PM0_PM0") (pintype "bidirectional"))
    )
    (net (code "140") (name "unconnected-(U$1-PadPM1)") (class "Default")
      (node (ref "U$1") (pin "PM1") (pinfunction "PM1_PM1") (pintype "bidirectional"))
    )
    (net (code "141") (name "unconnected-(U$1-PadPM2)") (class "Default")
      (node (ref "U$1") (pin "PM2") (pinfunction "PM2_PM2") (pintype "bidirectional"))
    )
    (net (code "142") (name "unconnected-(U$1-PadPM3)") (class "Default")
      (node (ref "U$1") (pin "PM3") (pinfunction "PM3_PM3") (pintype "bidirectional"))
    )
    (net (code "143") (name "unconnected-(U$1-PadPM4)") (class "Default")
      (node (ref "U$1") (pin "PM4") (pinfunction "PM4_PM4") (pintype "bidirectional"))
    )
    (net (code "144") (name "unconnected-(U$1-PadPM5)") (class "Default")
      (node (ref "U$1") (pin "PM5") (pinfunction "PM5_PM5") (pintype "bidirectional"))
    )
    (net (code "145") (name "unconnected-(U$1-PadPM6)") (class "Default")
      (node (ref "U$1") (pin "PM6") (pinfunction "PM6_PM6") (pintype "bidirectional"))
    )
    (net (code "146") (name "unconnected-(U$1-PadPM7)") (class "Default")
      (node (ref "U$1") (pin "PM7") (pinfunction "PM7_PM7") (pintype "bidirectional"))
    )
    (net (code "147") (name "unconnected-(U$1-PadPN2)") (class "Default")
      (node (ref "U$1") (pin "PN2") (pinfunction "PN2_PN2") (pintype "bidirectional"))
    )
    (net (code "148") (name "unconnected-(U$1-PadPN4)") (class "Default")
      (node (ref "U$1") (pin "PN4") (pinfunction "PN4_PN4") (pintype "bidirectional"))
    )
    (net (code "149") (name "unconnected-(U$1-PadPN5)") (class "Default")
      (node (ref "U$1") (pin "PN5") (pinfunction "PN5_PN5") (pintype "bidirectional"))
    )
    (net (code "150") (name "unconnected-(U$1-PadPP4)") (class "Default")
      (node (ref "U$1") (pin "PP4") (pinfunction "PP4_PP4") (pintype "bidirectional"))
    )
    (net (code "151") (name "unconnected-(U$1-PadPQ0)") (class "Default")
      (node (ref "U$1") (pin "PQ0") (pinfunction "PQ0_PQ0") (pintype "bidirectional"))
    )
    (net (code "152") (name "unconnected-(U$1-PadPQ2{slash}PA3)") (class "Default")
      (node (ref "U$1") (pin "PQ2/PA3") (pinfunction "PQ2/PA3_PQ2/PA3") (pintype "bidirectional"))
    )
    (net (code "153") (name "unconnected-(U$1-PadPQ3{slash}PA2)") (class "Default")
      (node (ref "U$1") (pin "PQ3/PA2") (pinfunction "PQ3/PA2_PQ3/PA2") (pintype "bidirectional"))
    )
    (net (code "154") (name "unconnected-(U$5-Pad4)") (class "Default")
      (node (ref "U$5") (pin "4") (pinfunction "4_4") (pintype "bidirectional"))
    )
    (net (code "155") (name "unconnected-(U$5-Pad5)") (class "Default")
      (node (ref "U$5") (pin "5") (pinfunction "5_5") (pintype "bidirectional"))
    )
    (net (code "156") (name "unconnected-(U$6-Pad4)") (class "Default")
      (node (ref "U$6") (pin "4") (pinfunction "4_4") (pintype "bidirectional"))
    )
    (net (code "157") (name "unconnected-(U$6-Pad5)") (class "Default")
      (node (ref "U$6") (pin "5") (pinfunction "5_5") (pintype "bidirectional"))
    )
  )
)
